# stages_v70.net
KiCad netlist of a schematic drawn in EAGLE
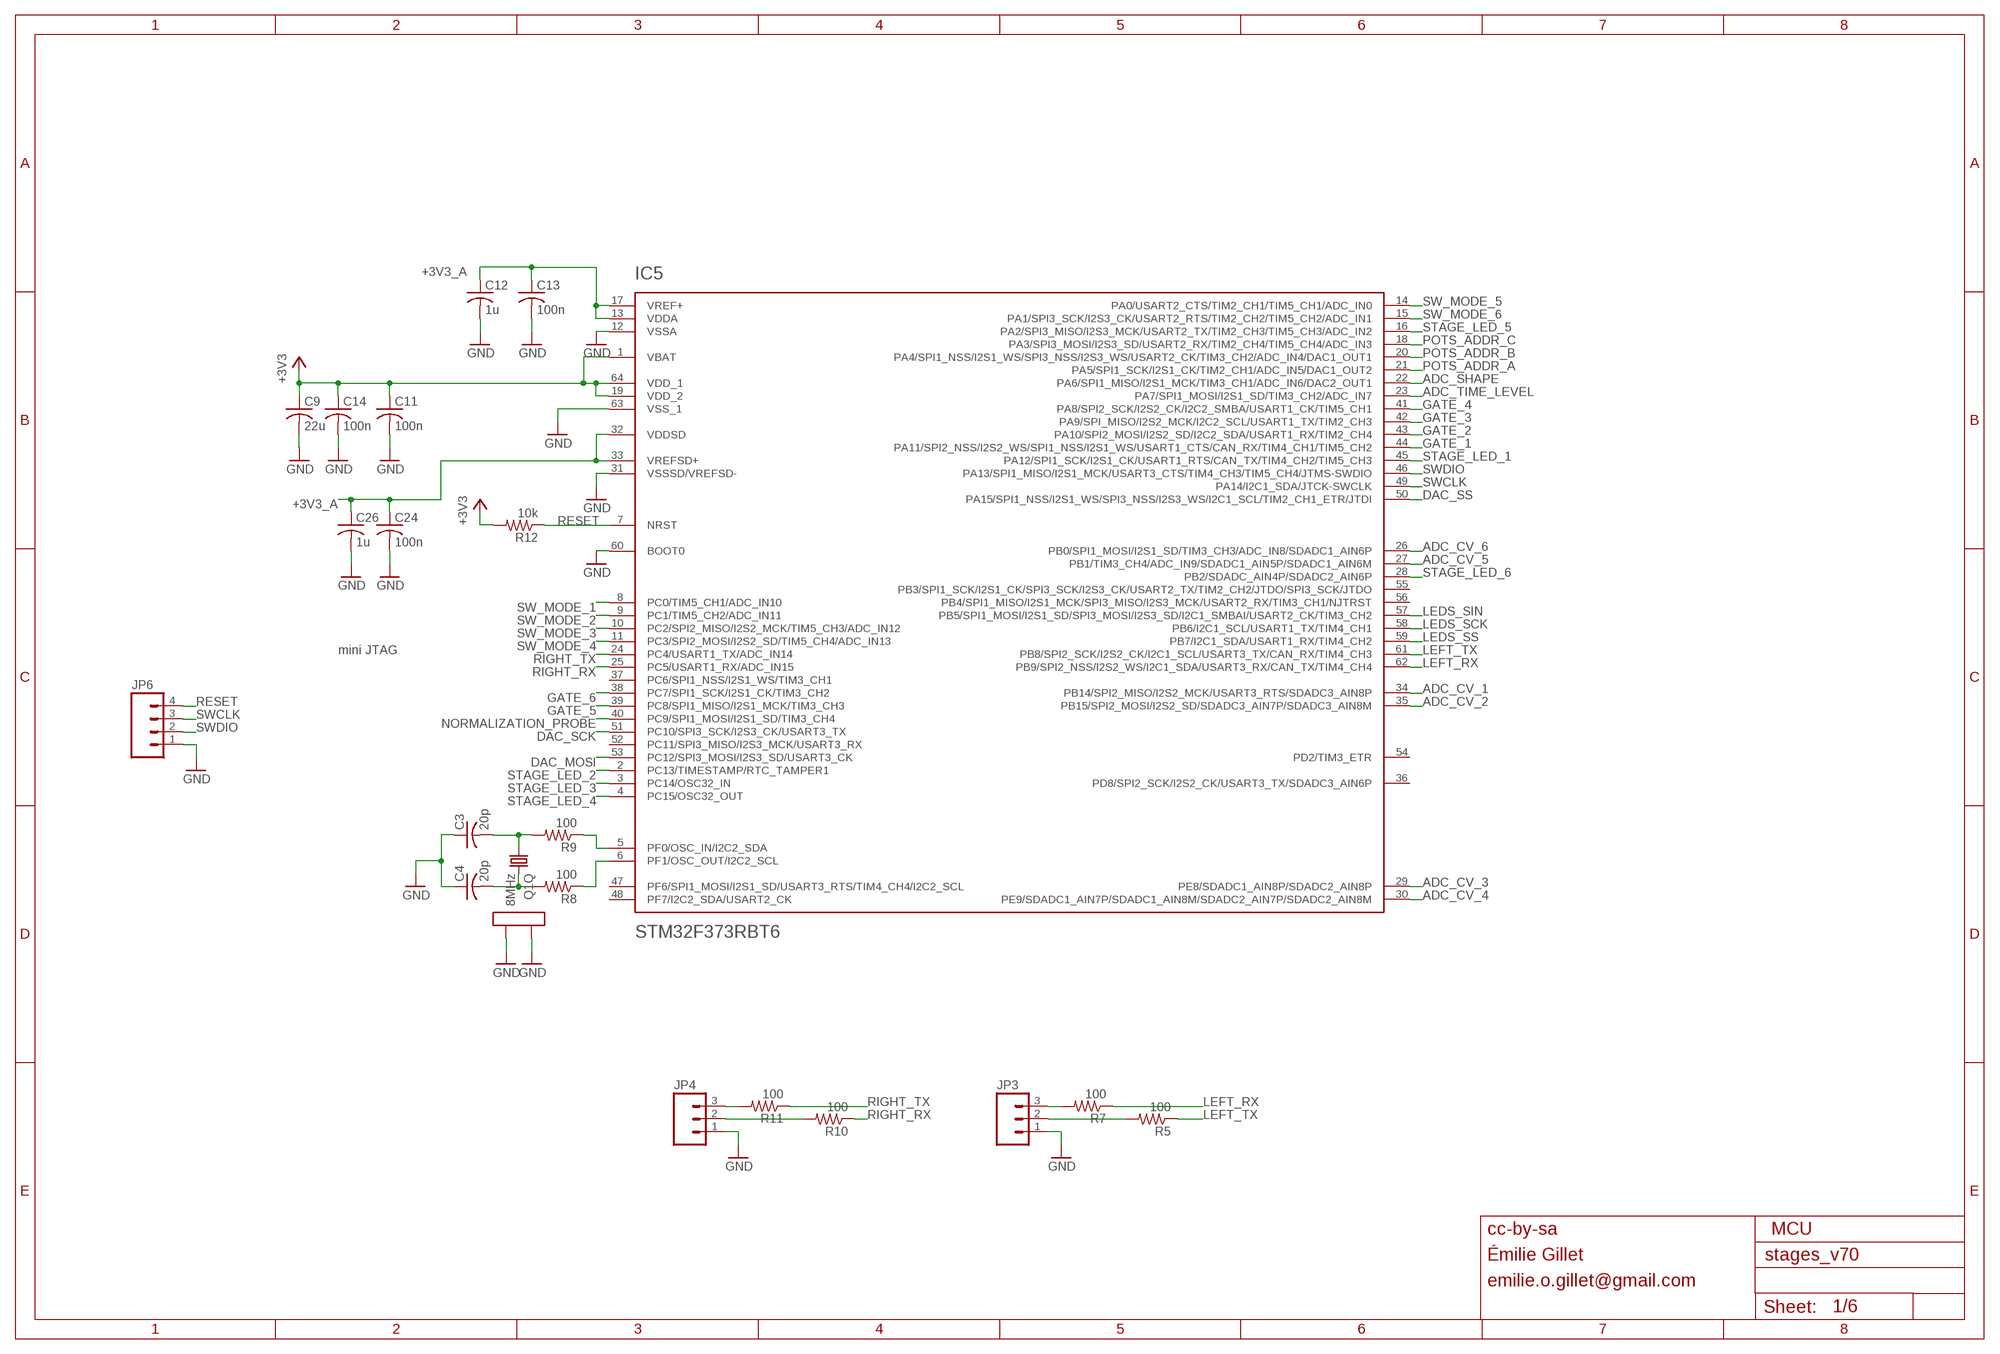
[diagram p0: schematic, sheet 1]
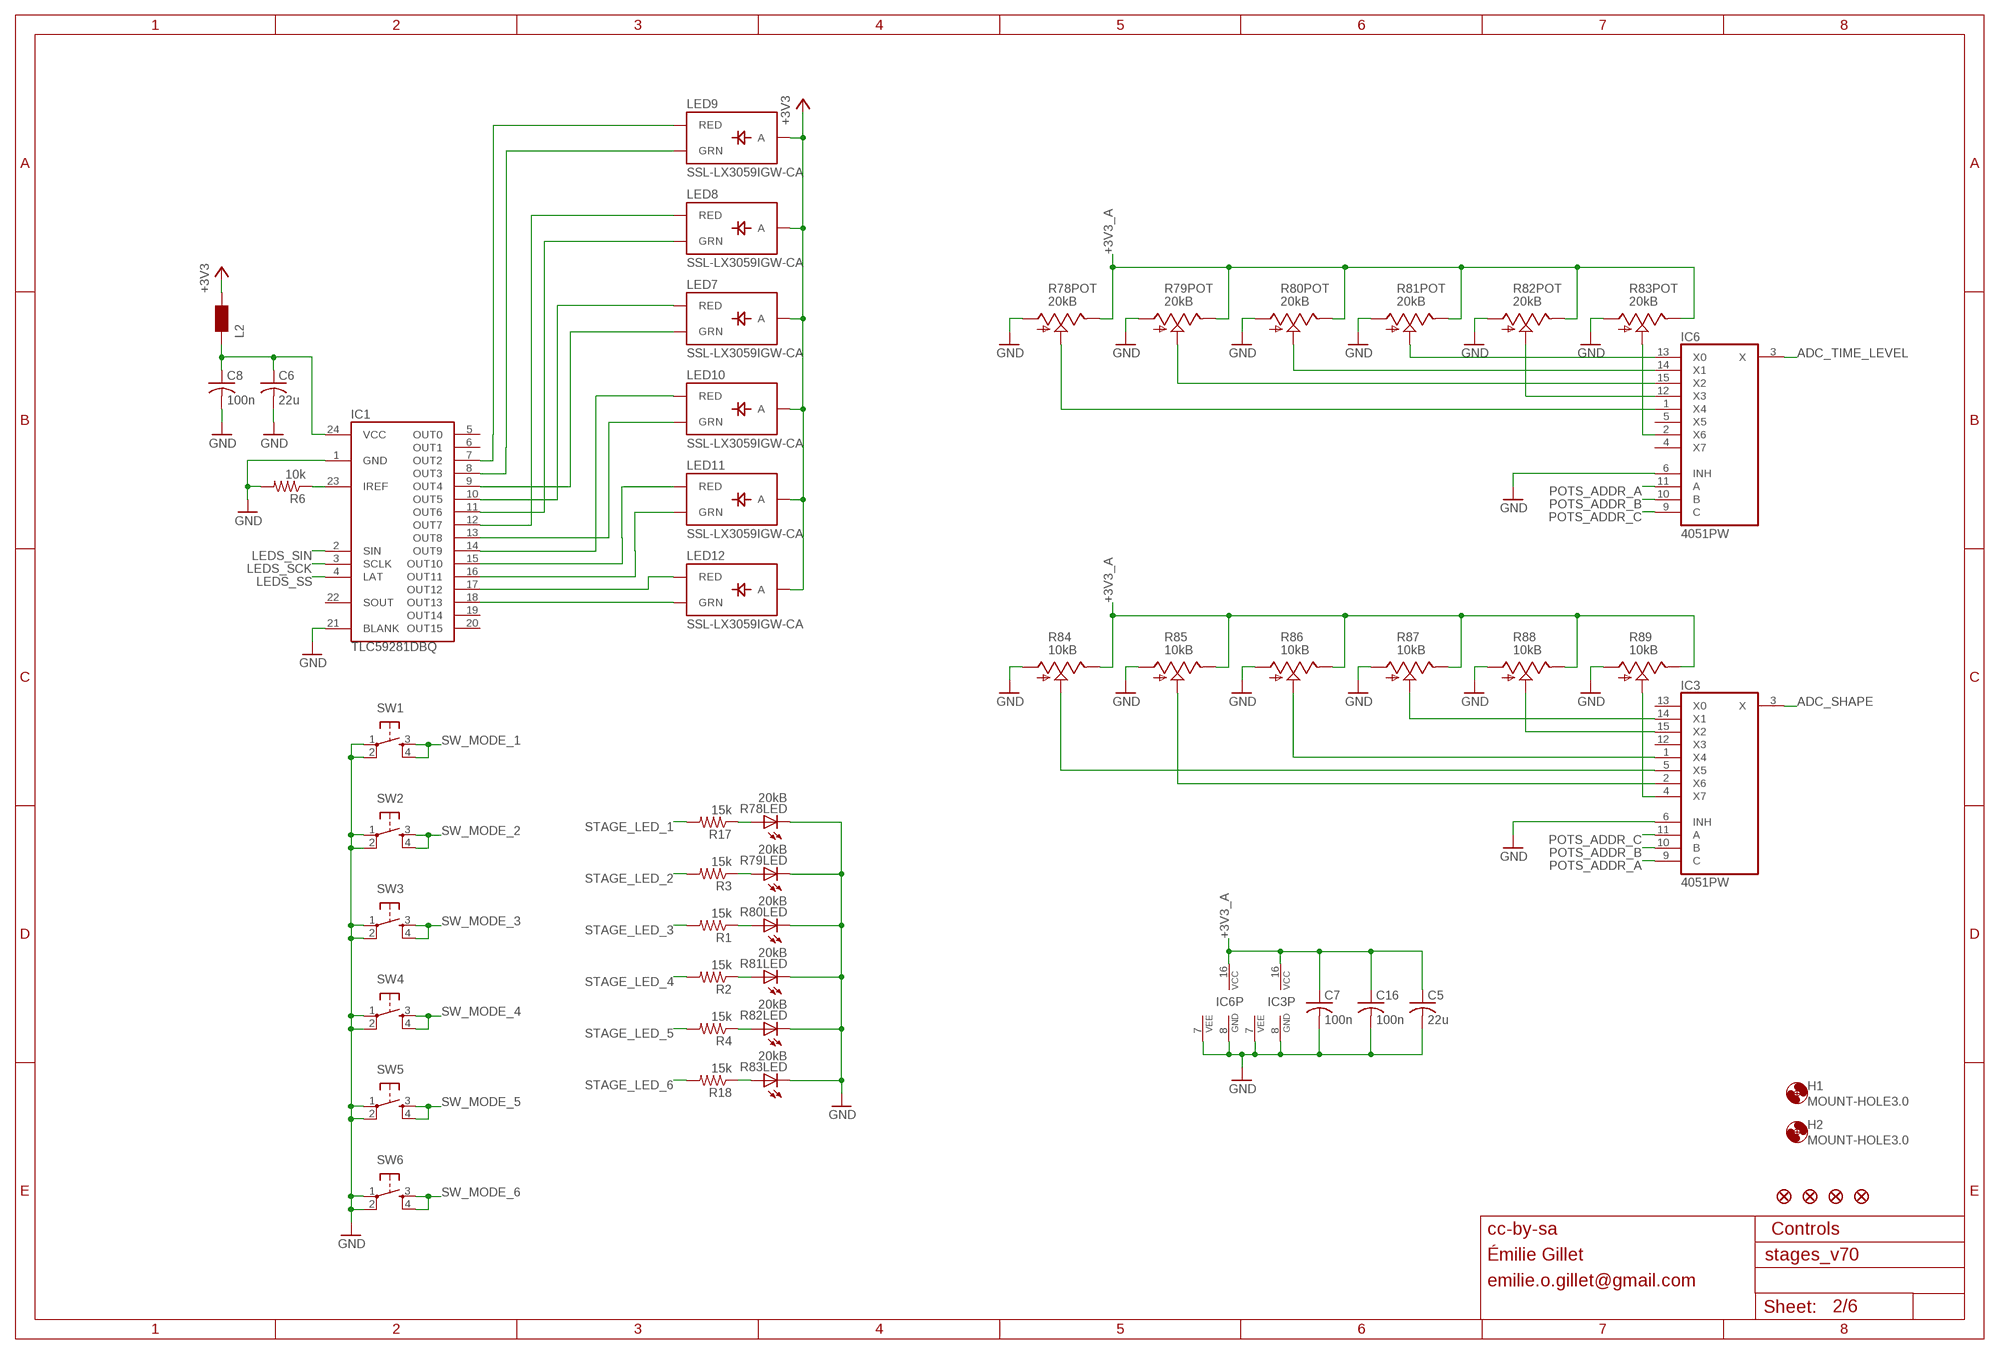
[diagram p1: schematic, sheet 2]
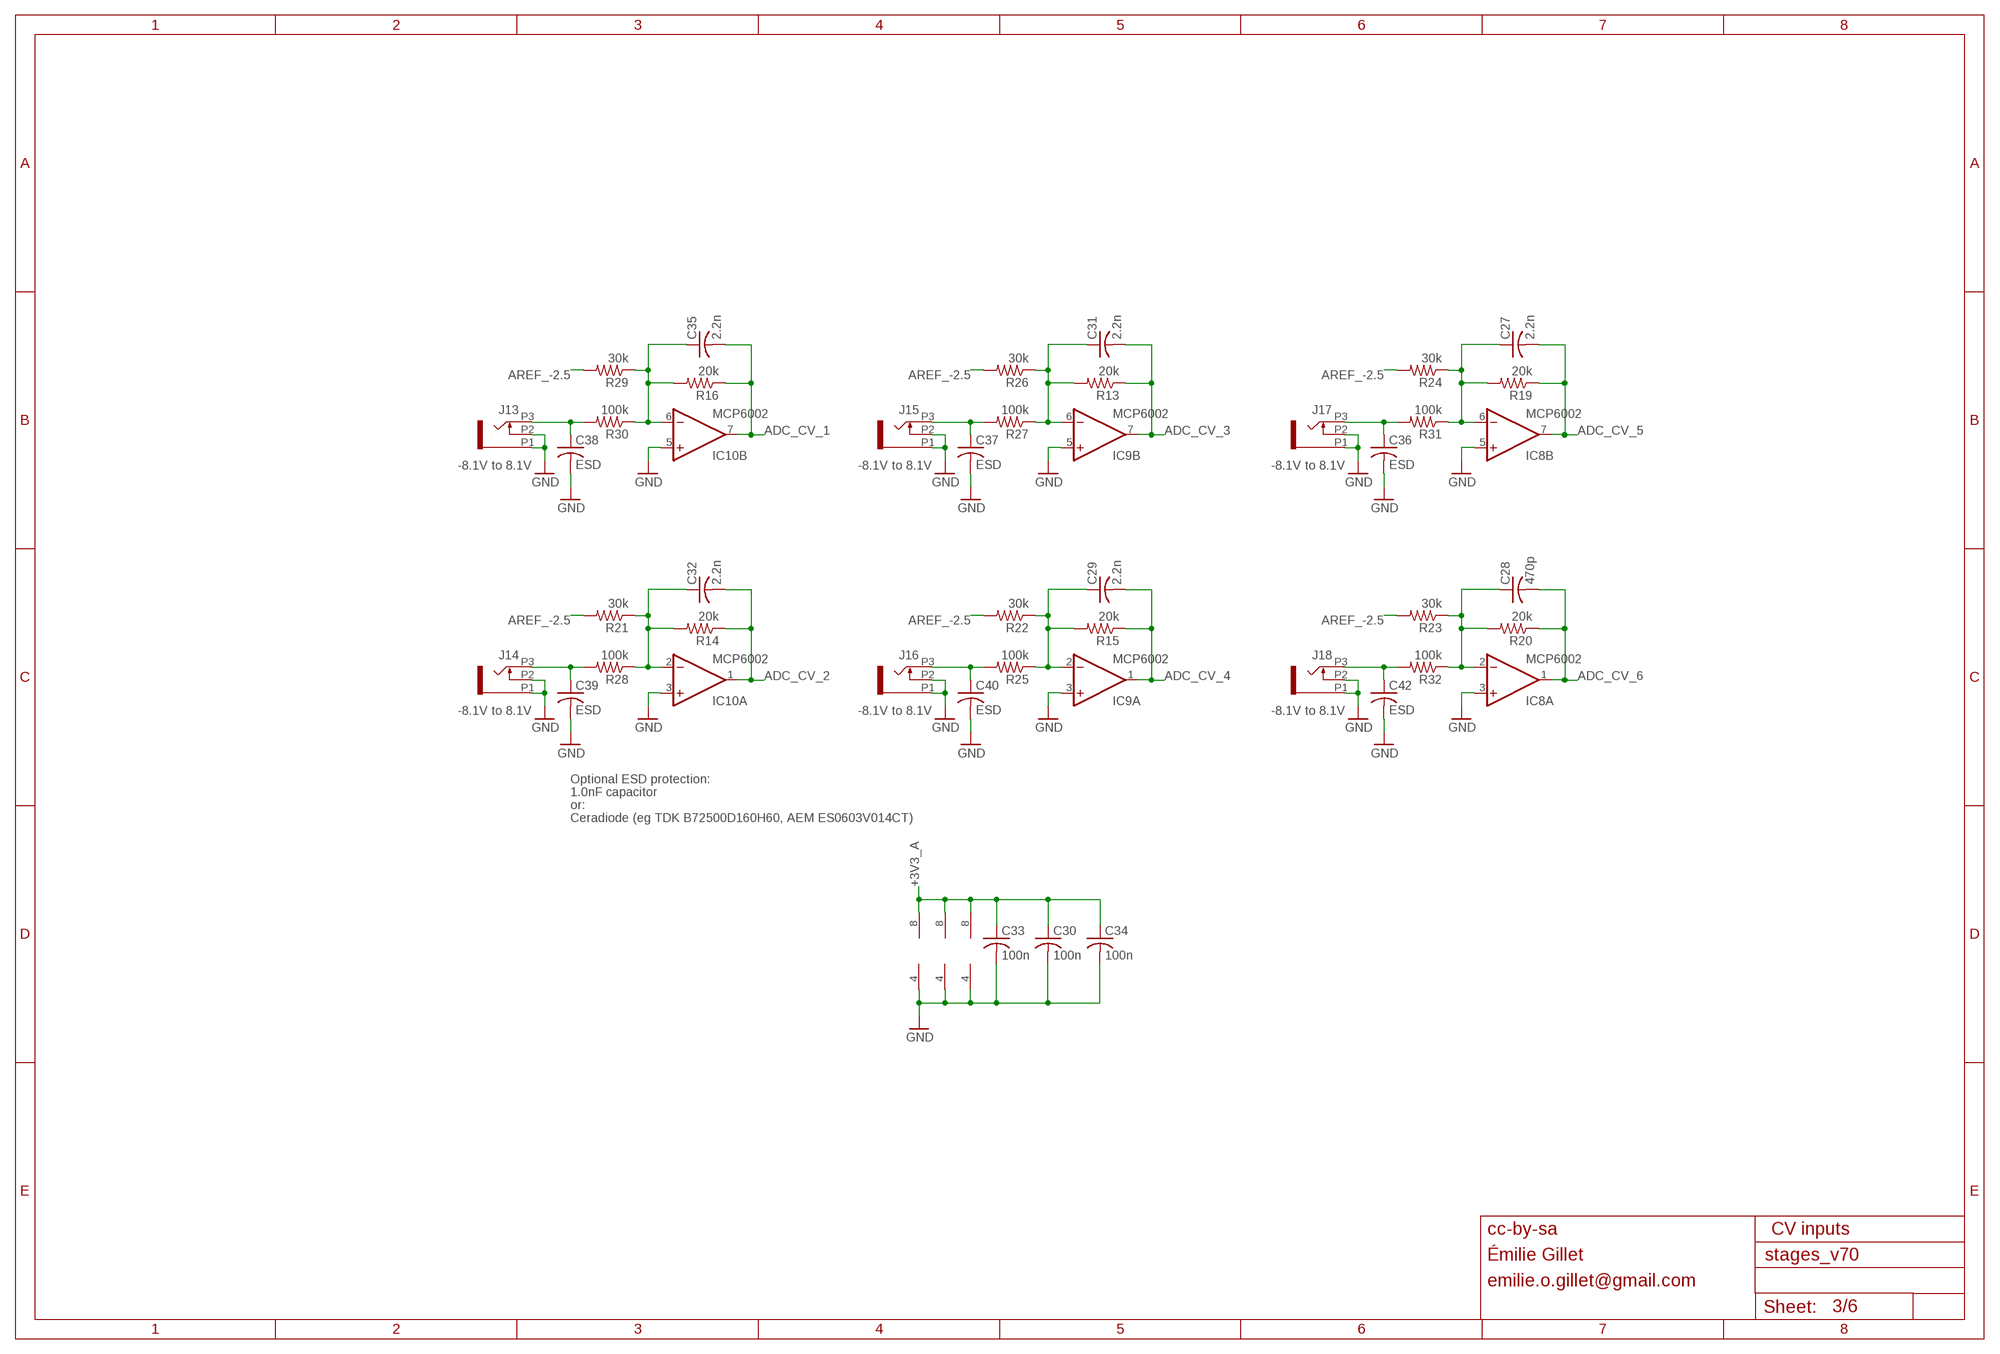
[diagram p2: schematic, sheet 3]
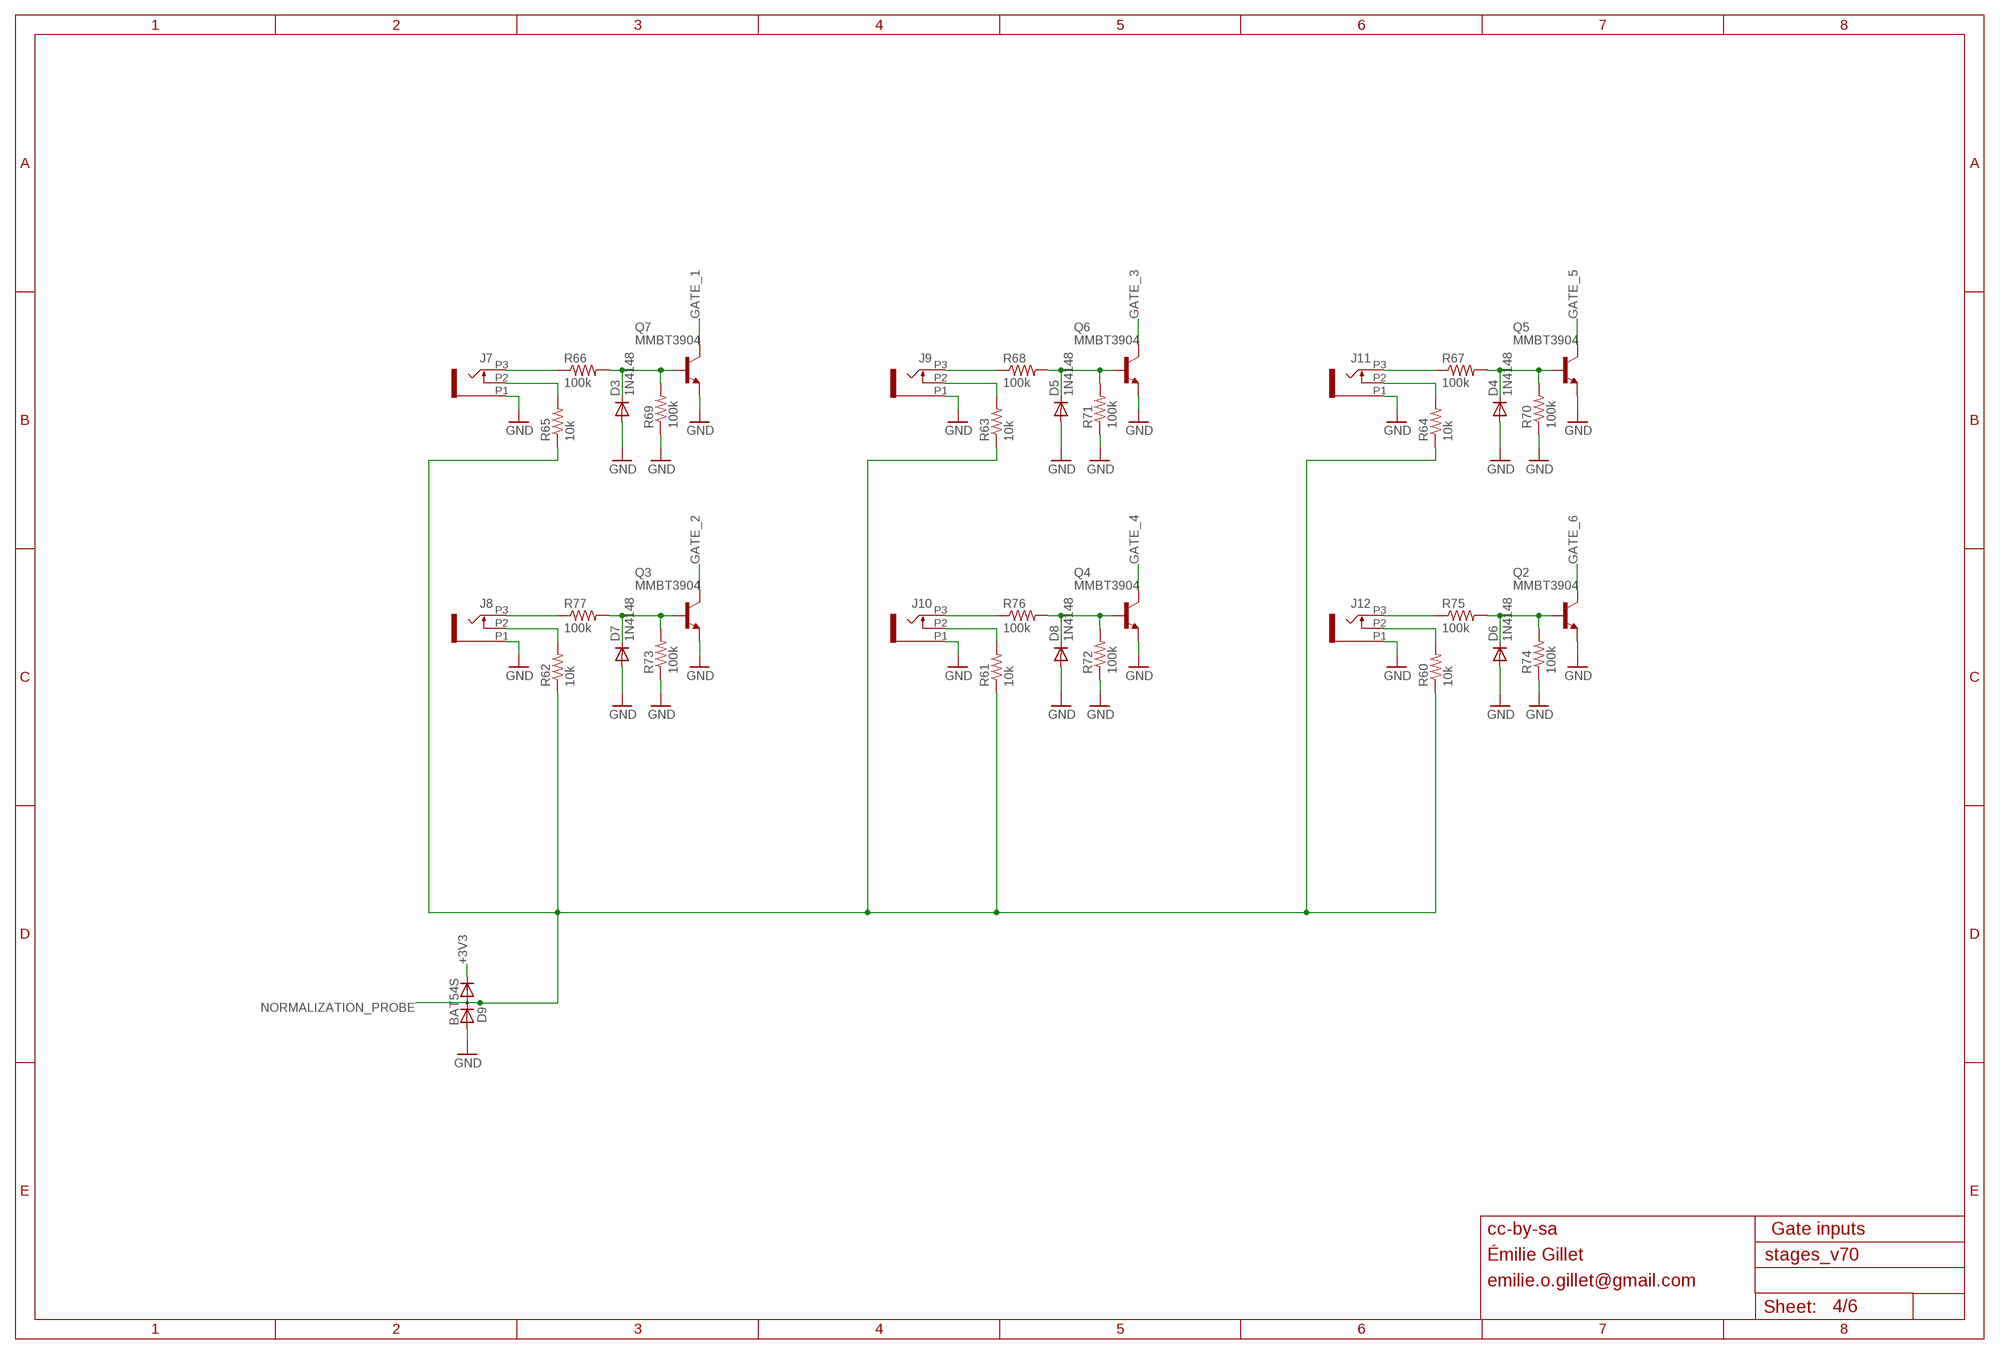
[diagram p3: schematic, sheet 4]
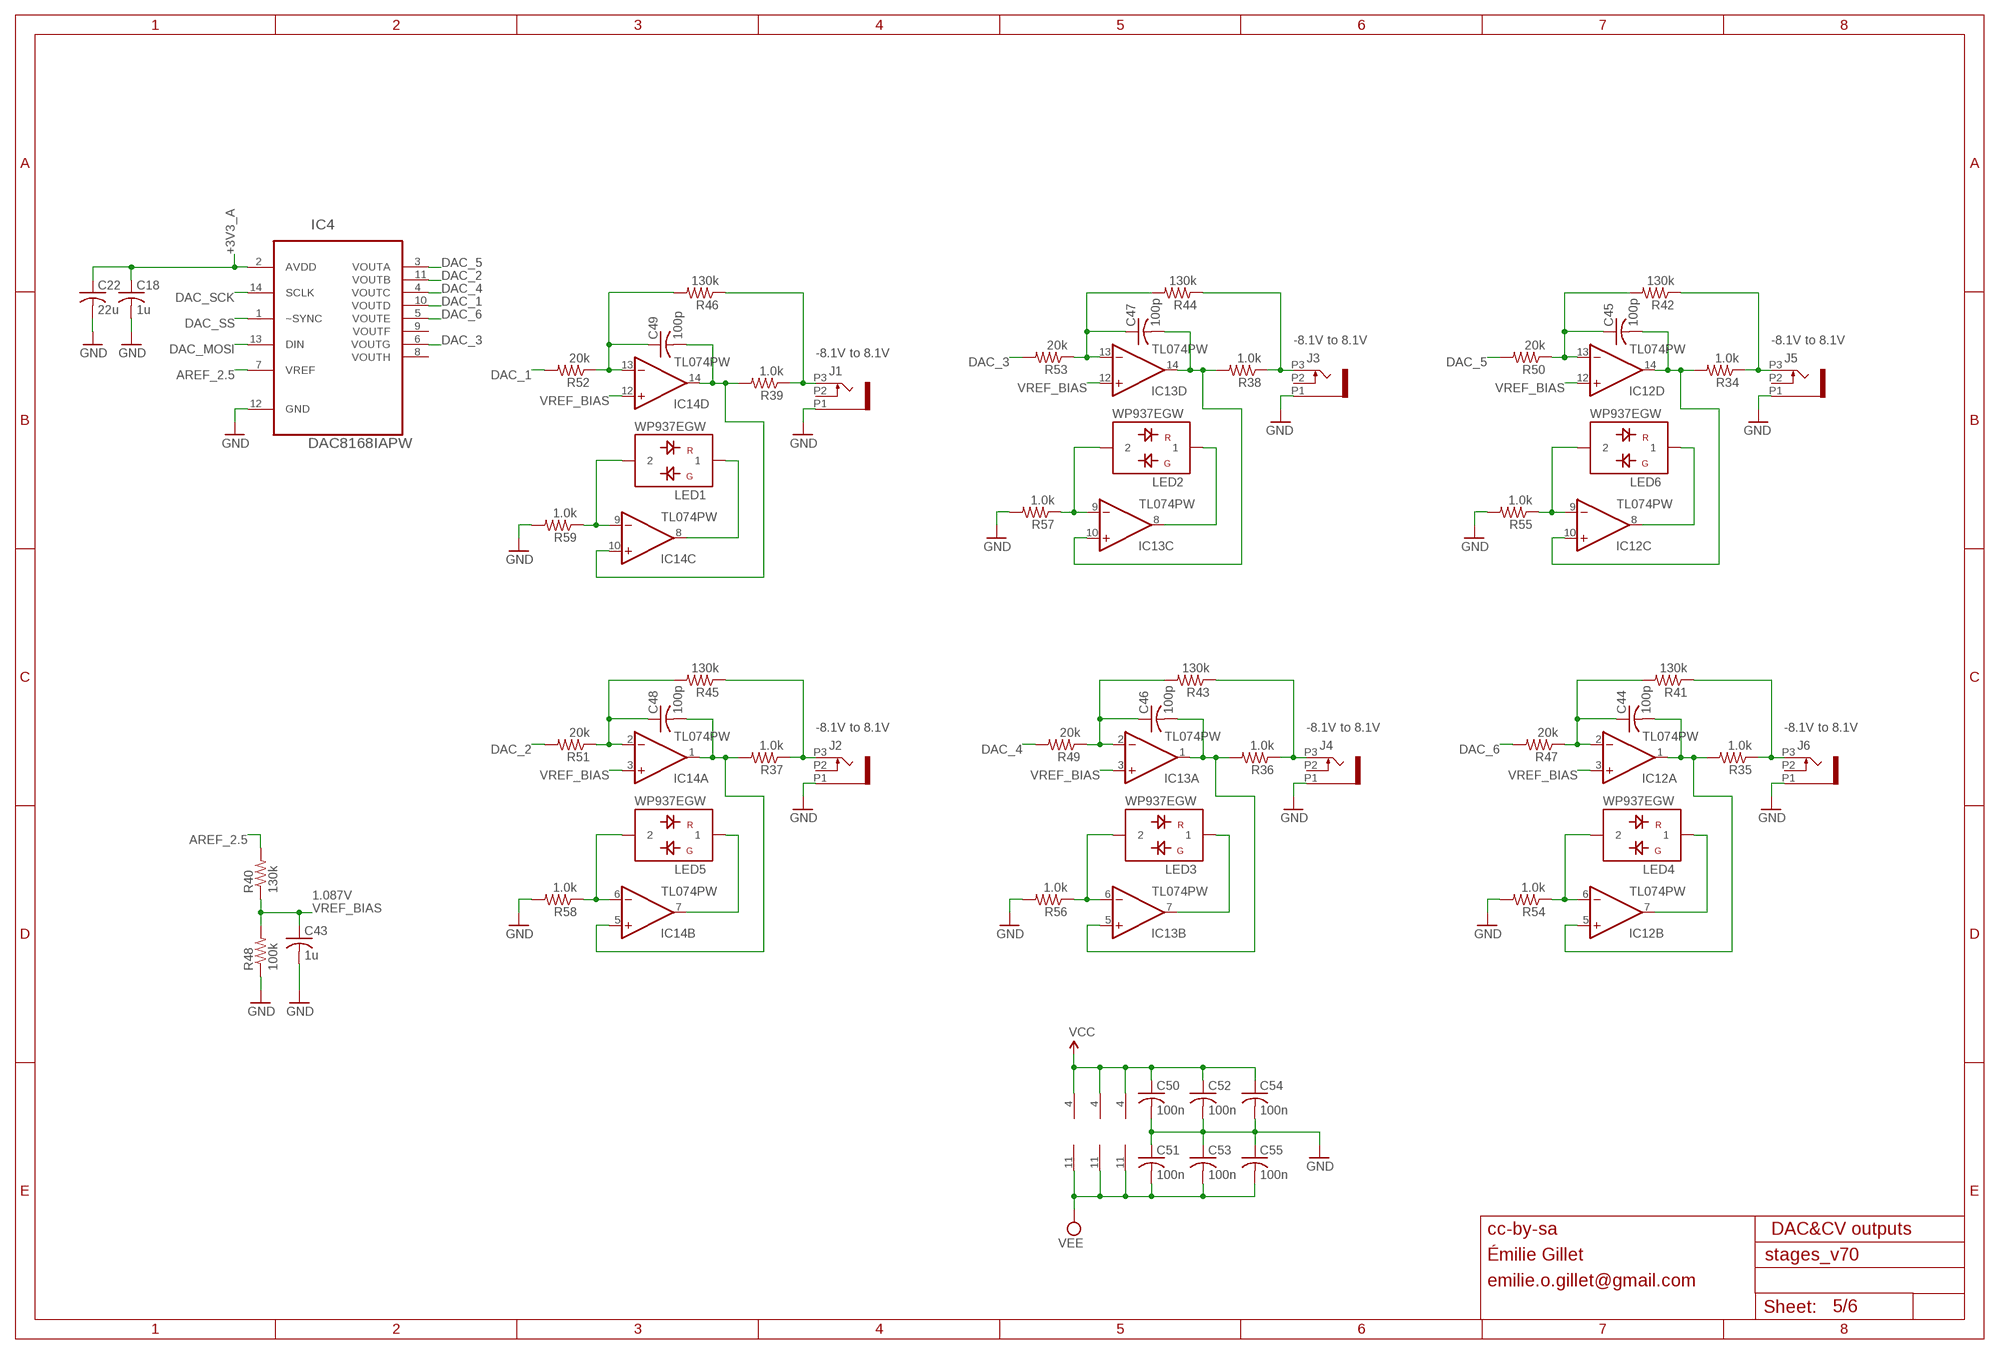
[diagram p4: schematic, sheet 5]
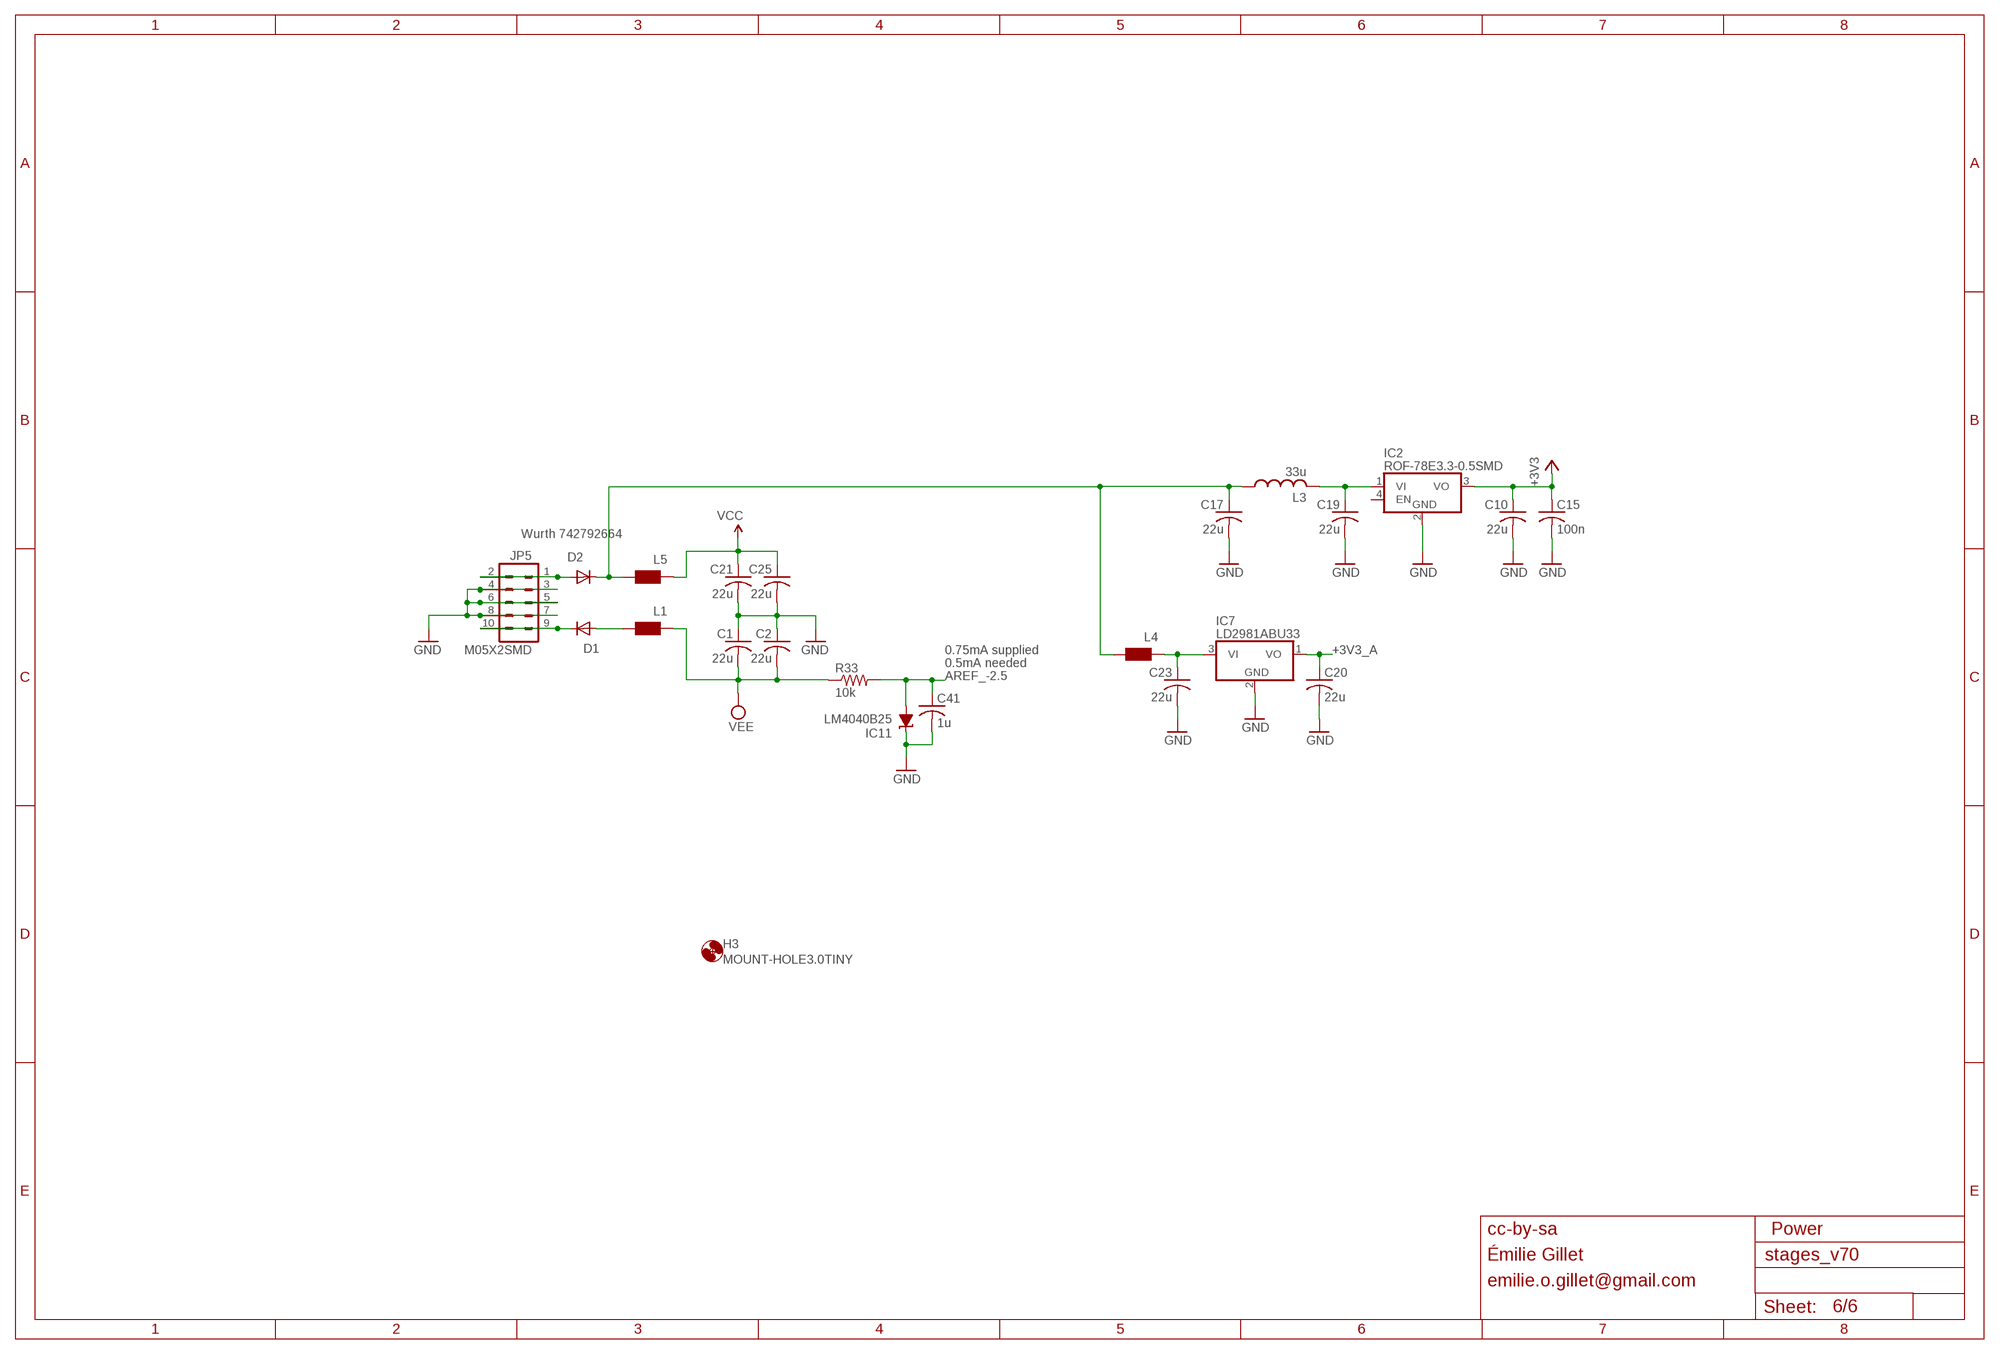
[diagram p5: schematic, sheet 6]

(export (version "E")
  (design (tool "Eeschema 10.0.6"))
  (components
    (comp (ref "C18")
      (value "1u")
      (footprint "eagle-import:C0402")
      (libsource (lib "eagle-import") (part "C-USC0402"))
    )
    (comp (ref "C22")
      (value "22u")
      (footprint "eagle-import:C1206")
      (libsource (lib "eagle-import") (part "C-USC1206"))
    )
    (comp (ref "C43")
      (value "1u")
      (footprint "eagle-import:C0402")
      (libsource (lib "eagle-import") (part "C-USC0402"))
    )
    (comp (ref "C44")
      (value "100p")
      (footprint "eagle-import:C0402")
      (libsource (lib "eagle-import") (part "C-USC0402"))
    )
    (comp (ref "C45")
      (value "100p")
      (footprint "eagle-import:C0402")
      (libsource (lib "eagle-import") (part "C-USC0402"))
    )
    (comp (ref "C46")
      (value "100p")
      (footprint "eagle-import:C0402")
      (libsource (lib "eagle-import") (part "C-USC0402"))
    )
    (comp (ref "C47")
      (value "100p")
      (footprint "eagle-import:C0402")
      (libsource (lib "eagle-import") (part "C-USC0402"))
    )
    (comp (ref "C48")
      (value "100p")
      (footprint "eagle-import:C0402")
      (libsource (lib "eagle-import") (part "C-USC0402"))
    )
    (comp (ref "C49")
      (value "100p")
      (footprint "eagle-import:C0402")
      (libsource (lib "eagle-import") (part "C-USC0402"))
    )
    (comp (ref "C50")
      (value "100n")
      (footprint "eagle-import:C0402")
      (libsource (lib "eagle-import") (part "C-USC0402"))
    )
    (comp (ref "C51")
      (value "100n")
      (footprint "eagle-import:C0402")
      (libsource (lib "eagle-import") (part "C-USC0402"))
    )
    (comp (ref "C52")
      (value "100n")
      (footprint "eagle-import:C0402")
      (libsource (lib "eagle-import") (part "C-USC0402"))
    )
    (comp (ref "C53")
      (value "100n")
      (footprint "eagle-import:C0402")
      (libsource (lib "eagle-import") (part "C-USC0402"))
    )
    (comp (ref "C54")
      (value "100n")
      (footprint "eagle-import:C0402")
      (libsource (lib "eagle-import") (part "C-USC0402"))
    )
    (comp (ref "C55")
      (value "100n")
      (footprint "eagle-import:C0402")
      (libsource (lib "eagle-import") (part "C-USC0402"))
    )
    (comp (ref "IC4")
      (value "DAC8168IAPW")
      (footprint "eagle-import:RPDSOG14")
      (libsource (lib "eagle-import") (part "DAC8168PW"))
    )
    (comp (ref "IC12")
      (value "TL074PW")
      (footprint "eagle-import:TSSOP14_065")
      (libsource (lib "eagle-import") (part "TL074PW"))
    )
    (comp (ref "IC13")
      (value "TL074PW")
      (footprint "eagle-import:TSSOP14_065")
      (libsource (lib "eagle-import") (part "TL074PW"))
    )
    (comp (ref "IC14")
      (value "TL074PW")
      (footprint "eagle-import:TSSOP14_065")
      (libsource (lib "eagle-import") (part "TL074PW"))
    )
    (comp (ref "J1")
      (value "PJ301_THONKICONN6")
      (footprint "eagle-import:WQP_PJ_301M6")
      (libsource (lib "eagle-import") (part "PJ301_THONKICONN6"))
    )
    (comp (ref "J2")
      (value "PJ301_THONKICONN6")
      (footprint "eagle-import:WQP_PJ_301M6")
      (libsource (lib "eagle-import") (part "PJ301_THONKICONN6"))
    )
    (comp (ref "J3")
      (value "PJ301_THONKICONN6")
      (footprint "eagle-import:WQP_PJ_301M6")
      (libsource (lib "eagle-import") (part "PJ301_THONKICONN6"))
    )
    (comp (ref "J4")
      (value "PJ301_THONKICONN6")
      (footprint "eagle-import:WQP_PJ_301M6")
      (libsource (lib "eagle-import") (part "PJ301_THONKICONN6"))
    )
    (comp (ref "J5")
      (value "PJ301_THONKICONN6")
      (footprint "eagle-import:WQP_PJ_301M6")
      (libsource (lib "eagle-import") (part "PJ301_THONKICONN6"))
    )
    (comp (ref "J6")
      (value "PJ301_THONKICONN6")
      (footprint "eagle-import:WQP_PJ_301M6")
      (libsource (lib "eagle-import") (part "PJ301_THONKICONN6"))
    )
    (comp (ref "LED1")
      (value "WP937EGW")
      (footprint "eagle-import:LED3MM")
      (libsource (lib "eagle-import") (part "LED-BICOLOR-SHARED-THROUGHHOLE"))
    )
    (comp (ref "LED2")
      (value "WP937EGW")
      (footprint "eagle-import:LED3MM")
      (libsource (lib "eagle-import") (part "LED-BICOLOR-SHARED-THROUGHHOLE"))
    )
    (comp (ref "LED3")
      (value "WP937EGW")
      (footprint "eagle-import:LED3MM")
      (libsource (lib "eagle-import") (part "LED-BICOLOR-SHARED-THROUGHHOLE"))
    )
    (comp (ref "LED4")
      (value "WP937EGW")
      (footprint "eagle-import:LED3MM")
      (libsource (lib "eagle-import") (part "LED-BICOLOR-SHARED-THROUGHHOLE"))
    )
    (comp (ref "LED5")
      (value "WP937EGW")
      (footprint "eagle-import:LED3MM")
      (libsource (lib "eagle-import") (part "LED-BICOLOR-SHARED-THROUGHHOLE"))
    )
    (comp (ref "LED6")
      (value "WP937EGW")
      (footprint "eagle-import:LED3MM")
      (libsource (lib "eagle-import") (part "LED-BICOLOR-SHARED-THROUGHHOLE"))
    )
    (comp (ref "R34")
      (value "1.0k")
      (footprint "eagle-import:R0603")
      (libsource (lib "eagle-import") (part "R-US_R0603"))
    )
    (comp (ref "R35")
      (value "1.0k")
      (footprint "eagle-import:R0603")
      (libsource (lib "eagle-import") (part "R-US_R0603"))
    )
    (comp (ref "R36")
      (value "1.0k")
      (footprint "eagle-import:R0603")
      (libsource (lib "eagle-import") (part "R-US_R0603"))
    )
    (comp (ref "R37")
      (value "1.0k")
      (footprint "eagle-import:R0603")
      (libsource (lib "eagle-import") (part "R-US_R0603"))
    )
    (comp (ref "R38")
      (value "1.0k")
      (footprint "eagle-import:R0603")
      (libsource (lib "eagle-import") (part "R-US_R0603"))
    )
    (comp (ref "R39")
      (value "1.0k")
      (footprint "eagle-import:R0603")
      (libsource (lib "eagle-import") (part "R-US_R0603"))
    )
    (comp (ref "R40")
      (value "130k")
      (footprint "eagle-import:R0402")
      (libsource (lib "eagle-import") (part "R-US_R0402"))
    )
    (comp (ref "R41")
      (value "130k")
      (footprint "eagle-import:R0402")
      (libsource (lib "eagle-import") (part "R-US_R0402"))
    )
    (comp (ref "R42")
      (value "130k")
      (footprint "eagle-import:R0402")
      (libsource (lib "eagle-import") (part "R-US_R0402"))
    )
    (comp (ref "R43")
      (value "130k")
      (footprint "eagle-import:R0402")
      (libsource (lib "eagle-import") (part "R-US_R0402"))
    )
    (comp (ref "R44")
      (value "130k")
      (footprint "eagle-import:R0402")
      (libsource (lib "eagle-import") (part "R-US_R0402"))
    )
    (comp (ref "R45")
      (value "130k")
      (footprint "eagle-import:R0402")
      (libsource (lib "eagle-import") (part "R-US_R0402"))
    )
    (comp (ref "R46")
      (value "130k")
      (footprint "eagle-import:R0402")
      (libsource (lib "eagle-import") (part "R-US_R0402"))
    )
    (comp (ref "R47")
      (value "20k")
      (footprint "eagle-import:R0402")
      (libsource (lib "eagle-import") (part "R-US_R0402"))
    )
    (comp (ref "R48")
      (value "100k")
      (footprint "eagle-import:R0402")
      (libsource (lib "eagle-import") (part "R-US_R0402"))
    )
    (comp (ref "R49")
      (value "20k")
      (footprint "eagle-import:R0402")
      (libsource (lib "eagle-import") (part "R-US_R0402"))
    )
    (comp (ref "R50")
      (value "20k")
      (footprint "eagle-import:R0402")
      (libsource (lib "eagle-import") (part "R-US_R0402"))
    )
    (comp (ref "R51")
      (value "20k")
      (footprint "eagle-import:R0402")
      (libsource (lib "eagle-import") (part "R-US_R0402"))
    )
    (comp (ref "R52")
      (value "20k")
      (footprint "eagle-import:R0402")
      (libsource (lib "eagle-import") (part "R-US_R0402"))
    )
    (comp (ref "R53")
      (value "20k")
      (footprint "eagle-import:R0402")
      (libsource (lib "eagle-import") (part "R-US_R0402"))
    )
    (comp (ref "R54")
      (value "1.0k")
      (footprint "eagle-import:R0402")
      (libsource (lib "eagle-import") (part "R-US_R0402"))
    )
    (comp (ref "R55")
      (value "1.0k")
      (footprint "eagle-import:R0402")
      (libsource (lib "eagle-import") (part "R-US_R0402"))
    )
    (comp (ref "R56")
      (value "1.0k")
      (footprint "eagle-import:R0402")
      (libsource (lib "eagle-import") (part "R-US_R0402"))
    )
    (comp (ref "R57")
      (value "1.0k")
      (footprint "eagle-import:R0402")
      (libsource (lib "eagle-import") (part "R-US_R0402"))
    )
    (comp (ref "R58")
      (value "1.0k")
      (footprint "eagle-import:R0402")
      (libsource (lib "eagle-import") (part "R-US_R0402"))
    )
    (comp (ref "R59")
      (value "1.0k")
      (footprint "eagle-import:R0402")
      (libsource (lib "eagle-import") (part "R-US_R0402"))
    )
    (comp (ref "C27")
      (value "2.2n")
      (footprint "eagle-import:C0402")
      (libsource (lib "eagle-import") (part "C-USC0402"))
    )
    (comp (ref "C28")
      (value "470p")
      (footprint "eagle-import:C0402")
      (libsource (lib "eagle-import") (part "C-USC0402"))
    )
    (comp (ref "C29")
      (value "2.2n")
      (footprint "eagle-import:C0402")
      (libsource (lib "eagle-import") (part "C-USC0402"))
    )
    (comp (ref "C30")
      (value "100n")
      (footprint "eagle-import:C0402")
      (libsource (lib "eagle-import") (part "C-USC0402"))
    )
    (comp (ref "C31")
      (value "2.2n")
      (footprint "eagle-import:C0402")
      (libsource (lib "eagle-import") (part "C-USC0402"))
    )
    (comp (ref "C32")
      (value "2.2n")
      (footprint "eagle-import:C0402")
      (libsource (lib "eagle-import") (part "C-USC0402"))
    )
    (comp (ref "C33")
      (value "100n")
      (footprint "eagle-import:C0402")
      (libsource (lib "eagle-import") (part "C-USC0402"))
    )
    (comp (ref "C34")
      (value "100n")
      (footprint "eagle-import:C0402")
      (libsource (lib "eagle-import") (part "C-USC0402"))
    )
    (comp (ref "C35")
      (value "2.2n")
      (footprint "eagle-import:C0402")
      (libsource (lib "eagle-import") (part "C-USC0402"))
    )
    (comp (ref "C36")
      (value "ESD")
      (footprint "eagle-import:C0603")
      (libsource (lib "eagle-import") (part "C-USC0603"))
    )
    (comp (ref "C37")
      (value "ESD")
      (footprint "eagle-import:C0603")
      (libsource (lib "eagle-import") (part "C-USC0603"))
    )
    (comp (ref "C38")
      (value "ESD")
      (footprint "eagle-import:C0603")
      (libsource (lib "eagle-import") (part "C-USC0603"))
    )
    (comp (ref "C39")
      (value "ESD")
      (footprint "eagle-import:C0603")
      (libsource (lib "eagle-import") (part "C-USC0603"))
    )
    (comp (ref "C40")
      (value "ESD")
      (footprint "eagle-import:C0603")
      (libsource (lib "eagle-import") (part "C-USC0603"))
    )
    (comp (ref "C42")
      (value "ESD")
      (footprint "eagle-import:C0603")
      (libsource (lib "eagle-import") (part "C-USC0603"))
    )
    (comp (ref "IC8")
      (value "MCP6002")
      (footprint "eagle-import:MSOP-8")
      (libsource (lib "eagle-import") (part "OPA1652DGK"))
    )
    (comp (ref "IC9")
      (value "MCP6002")
      (footprint "eagle-import:MSOP-8")
      (libsource (lib "eagle-import") (part "OPA1652DGK"))
    )
    (comp (ref "IC10")
      (value "MCP6002")
      (footprint "eagle-import:MSOP-8")
      (libsource (lib "eagle-import") (part "OPA1652DGK"))
    )
    (comp (ref "J13")
      (value "PJ301_THONKICONN6")
      (footprint "eagle-import:WQP_PJ_301M6")
      (libsource (lib "eagle-import") (part "PJ301_THONKICONN6"))
    )
    (comp (ref "J14")
      (value "PJ301_THONKICONN6")
      (footprint "eagle-import:WQP_PJ_301M6")
      (libsource (lib "eagle-import") (part "PJ301_THONKICONN6"))
    )
    (comp (ref "J15")
      (value "PJ301_THONKICONN6")
      (footprint "eagle-import:WQP_PJ_301M6")
      (libsource (lib "eagle-import") (part "PJ301_THONKICONN6"))
    )
    (comp (ref "J16")
      (value "PJ301_THONKICONN6")
      (footprint "eagle-import:WQP_PJ_301M6")
      (libsource (lib "eagle-import") (part "PJ301_THONKICONN6"))
    )
    (comp (ref "J17")
      (value "PJ301_THONKICONN6")
      (footprint "eagle-import:WQP_PJ_301M6")
      (libsource (lib "eagle-import") (part "PJ301_THONKICONN6"))
    )
    (comp (ref "J18")
      (value "PJ301_THONKICONN6")
      (footprint "eagle-import:WQP_PJ_301M6")
      (libsource (lib "eagle-import") (part "PJ301_THONKICONN6"))
    )
    (comp (ref "R13")
      (value "20k")
      (footprint "eagle-import:R0402")
      (libsource (lib "eagle-import") (part "R-US_R0402"))
    )
    (comp (ref "R14")
      (value "20k")
      (footprint "eagle-import:R0402")
      (libsource (lib "eagle-import") (part "R-US_R0402"))
    )
    (comp (ref "R15")
      (value "20k")
      (footprint "eagle-import:R0402")
      (libsource (lib "eagle-import") (part "R-US_R0402"))
    )
    (comp (ref "R16")
      (value "20k")
      (footprint "eagle-import:R0402")
      (libsource (lib "eagle-import") (part "R-US_R0402"))
    )
    (comp (ref "R19")
      (value "20k")
      (footprint "eagle-import:R0402")
      (libsource (lib "eagle-import") (part "R-US_R0402"))
    )
    (comp (ref "R20")
      (value "20k")
      (footprint "eagle-import:R0402")
      (libsource (lib "eagle-import") (part "R-US_R0402"))
    )
    (comp (ref "R21")
      (value "30k")
      (footprint "eagle-import:R0402")
      (libsource (lib "eagle-import") (part "R-US_R0402"))
    )
    (comp (ref "R22")
      (value "30k")
      (footprint "eagle-import:R0402")
      (libsource (lib "eagle-import") (part "R-US_R0402"))
    )
    (comp (ref "R23")
      (value "30k")
      (footprint "eagle-import:R0402")
      (libsource (lib "eagle-import") (part "R-US_R0402"))
    )
    (comp (ref "R24")
      (value "30k")
      (footprint "eagle-import:R0402")
      (libsource (lib "eagle-import") (part "R-US_R0402"))
    )
    (comp (ref "R25")
      (value "100k")
      (footprint "eagle-import:R0402")
      (libsource (lib "eagle-import") (part "R-US_R0402"))
    )
    (comp (ref "R26")
      (value "30k")
      (footprint "eagle-import:R0402")
      (libsource (lib "eagle-import") (part "R-US_R0402"))
    )
    (comp (ref "R27")
      (value "100k")
      (footprint "eagle-import:R0402")
      (libsource (lib "eagle-import") (part "R-US_R0402"))
    )
    (comp (ref "R28")
      (value "100k")
      (footprint "eagle-import:R0402")
      (libsource (lib "eagle-import") (part "R-US_R0402"))
    )
    (comp (ref "R29")
      (value "30k")
      (footprint "eagle-import:R0402")
      (libsource (lib "eagle-import") (part "R-US_R0402"))
    )
    (comp (ref "R30")
      (value "100k")
      (footprint "eagle-import:R0402")
      (libsource (lib "eagle-import") (part "R-US_R0402"))
    )
    (comp (ref "R31")
      (value "100k")
      (footprint "eagle-import:R0402")
      (libsource (lib "eagle-import") (part "R-US_R0402"))
    )
    (comp (ref "R32")
      (value "100k")
      (footprint "eagle-import:R0402")
      (libsource (lib "eagle-import") (part "R-US_R0402"))
    )
    (comp (ref "C3")
      (value "20p")
      (footprint "eagle-import:C0402")
      (libsource (lib "eagle-import") (part "C-USC0402"))
    )
    (comp (ref "C4")
      (value "20p")
      (footprint "eagle-import:C0402")
      (libsource (lib "eagle-import") (part "C-USC0402"))
    )
    (comp (ref "C9")
      (value "22u")
      (footprint "eagle-import:C1206")
      (libsource (lib "eagle-import") (part "C-USC1206"))
    )
    (comp (ref "C11")
      (value "100n")
      (footprint "eagle-import:C0402")
      (libsource (lib "eagle-import") (part "C-USC0402"))
    )
    (comp (ref "C12")
      (value "1u")
      (footprint "eagle-import:C0402")
      (libsource (lib "eagle-import") (part "C-USC0402"))
    )
    (comp (ref "C13")
      (value "100n")
      (footprint "eagle-import:C0402")
      (libsource (lib "eagle-import") (part "C-USC0402"))
    )
    (comp (ref "C14")
      (value "100n")
      (footprint "eagle-import:C0402")
      (libsource (lib "eagle-import") (part "C-USC0402"))
    )
    (comp (ref "C24")
      (value "100n")
      (footprint "eagle-import:C0402")
      (libsource (lib "eagle-import") (part "C-USC0402"))
    )
    (comp (ref "C26")
      (value "1u")
      (footprint "eagle-import:C0402")
      (libsource (lib "eagle-import") (part "C-USC0402"))
    )
    (comp (ref "IC5")
      (value "STM32F373RBT6")
      (footprint "eagle-import:TQFP-10X10-64")
      (libsource (lib "eagle-import") (part "STM32F373R"))
    )
    (comp (ref "JP3")
      (value "M03PTH")
      (footprint "eagle-import:1X03")
      (libsource (lib "eagle-import") (part "M03PTH"))
    )
    (comp (ref "JP4")
      (value "M03PTH")
      (footprint "eagle-import:1X03")
      (libsource (lib "eagle-import") (part "M03PTH"))
    )
    (comp (ref "JP6")
      (value "M04PTH")
      (footprint "eagle-import:1X04")
      (libsource (lib "eagle-import") (part "M04PTH"))
    )
    (comp (ref "Q1")
      (value "8MHz")
      (footprint "eagle-import:CTS406")
      (libsource (lib "eagle-import") (part "CRYSTAL"))
    )
    (comp (ref "R5")
      (value "100")
      (footprint "eagle-import:R0402")
      (libsource (lib "eagle-import") (part "R-US_R0402"))
    )
    (comp (ref "R7")
      (value "100")
      (footprint "eagle-import:R0402")
      (libsource (lib "eagle-import") (part "R-US_R0402"))
    )
    (comp (ref "R8")
      (value "100")
      (footprint "eagle-import:R0402")
      (libsource (lib "eagle-import") (part "R-US_R0402"))
    )
    (comp (ref "R9")
      (value "100")
      (footprint "eagle-import:R0402")
      (libsource (lib "eagle-import") (part "R-US_R0402"))
    )
    (comp (ref "R10")
      (value "100")
      (footprint "eagle-import:R0402")
      (libsource (lib "eagle-import") (part "R-US_R0402"))
    )
    (comp (ref "R11")
      (value "100")
      (footprint "eagle-import:R0402")
      (libsource (lib "eagle-import") (part "R-US_R0402"))
    )
    (comp (ref "R12")
      (value "10k")
      (footprint "eagle-import:R0402")
      (libsource (lib "eagle-import") (part "R-US_R0402"))
    )
    (comp (ref "D3")
      (value "1N4148")
      (footprint "eagle-import:SOD523")
      (libsource (lib "eagle-import") (part "DIODE-SOD523"))
    )
    (comp (ref "D4")
      (value "1N4148")
      (footprint "eagle-import:SOD523")
      (libsource (lib "eagle-import") (part "DIODE-SOD523"))
    )
    (comp (ref "D5")
      (value "1N4148")
      (footprint "eagle-import:SOD523")
      (libsource (lib "eagle-import") (part "DIODE-SOD523"))
    )
    (comp (ref "D6")
      (value "1N4148")
      (footprint "eagle-import:SOD523")
      (libsource (lib "eagle-import") (part "DIODE-SOD523"))
    )
    (comp (ref "D7")
      (value "1N4148")
      (footprint "eagle-import:SOD523")
      (libsource (lib "eagle-import") (part "DIODE-SOD523"))
    )
    (comp (ref "D8")
      (value "1N4148")
      (footprint "eagle-import:SOD523")
      (libsource (lib "eagle-import") (part "DIODE-SOD523"))
    )
    (comp (ref "D9")
      (value "BAT54S")
      (footprint "eagle-import:SOT23")
      (libsource (lib "eagle-import") (part "DIODE_2CACA-SOT23"))
    )
    (comp (ref "J7")
      (value "PJ301_THONKICONN6")
      (footprint "eagle-import:WQP_PJ_301M6")
      (libsource (lib "eagle-import") (part "PJ301_THONKICONN6"))
    )
    (comp (ref "J8")
      (value "PJ301_THONKICONN6")
      (footprint "eagle-import:WQP_PJ_301M6")
      (libsource (lib "eagle-import") (part "PJ301_THONKICONN6"))
    )
    (comp (ref "J9")
      (value "PJ301_THONKICONN6")
      (footprint "eagle-import:WQP_PJ_301M6")
      (libsource (lib "eagle-import") (part "PJ301_THONKICONN6"))
    )
    (comp (ref "J10")
      (value "PJ301_THONKICONN6")
      (footprint "eagle-import:WQP_PJ_301M6")
      (libsource (lib "eagle-import") (part "PJ301_THONKICONN6"))
    )
    (comp (ref "J11")
      (value "PJ301_THONKICONN6")
      (footprint "eagle-import:WQP_PJ_301M6")
      (libsource (lib "eagle-import") (part "PJ301_THONKICONN6"))
    )
    (comp (ref "J12")
      (value "PJ301_THONKICONN6")
      (footprint "eagle-import:WQP_PJ_301M6")
      (libsource (lib "eagle-import") (part "PJ301_THONKICONN6"))
    )
    (comp (ref "Q2")
      (value "MMBT3904")
      (footprint "eagle-import:SOT23-BEC")
      (libsource (lib "eagle-import") (part "-NPN-SOT23-BECMMBT3904LT1"))
    )
    (comp (ref "Q3")
      (value "MMBT3904")
      (footprint "eagle-import:SOT23-BEC")
      (libsource (lib "eagle-import") (part "-NPN-SOT23-BECMMBT3904LT1"))
    )
    (comp (ref "Q4")
      (value "MMBT3904")
      (footprint "eagle-import:SOT23-BEC")
      (libsource (lib "eagle-import") (part "-NPN-SOT23-BECMMBT3904LT1"))
    )
    (comp (ref "Q5")
      (value "MMBT3904")
      (footprint "eagle-import:SOT23-BEC")
      (libsource (lib "eagle-import") (part "-NPN-SOT23-BECMMBT3904LT1"))
    )
    (comp (ref "Q6")
      (value "MMBT3904")
      (footprint "eagle-import:SOT23-BEC")
      (libsource (lib "eagle-import") (part "-NPN-SOT23-BECMMBT3904LT1"))
    )
    (comp (ref "Q7")
      (value "MMBT3904")
      (footprint "eagle-import:SOT23-BEC")
      (libsource (lib "eagle-import") (part "-NPN-SOT23-BECMMBT3904LT1"))
    )
    (comp (ref "R60")
      (value "10k")
      (footprint "eagle-import:R0402")
      (libsource (lib "eagle-import") (part "R-US_R0402"))
    )
    (comp (ref "R61")
      (value "10k")
      (footprint "eagle-import:R0402")
      (libsource (lib "eagle-import") (part "R-US_R0402"))
    )
    (comp (ref "R62")
      (value "10k")
      (footprint "eagle-import:R0402")
      (libsource (lib "eagle-import") (part "R-US_R0402"))
    )
    (comp (ref "R63")
      (value "10k")
      (footprint "eagle-import:R0402")
      (libsource (lib "eagle-import") (part "R-US_R0402"))
    )
    (comp (ref "R64")
      (value "10k")
      (footprint "eagle-import:R0402")
      (libsource (lib "eagle-import") (part "R-US_R0402"))
    )
    (comp (ref "R65")
      (value "10k")
      (footprint "eagle-import:R0402")
      (libsource (lib "eagle-import") (part "R-US_R0402"))
    )
    (comp (ref "R66")
      (value "100k")
      (footprint "eagle-import:R0402")
      (libsource (lib "eagle-import") (part "R-US_R0402"))
    )
    (comp (ref "R67")
      (value "100k")
      (footprint "eagle-import:R0402")
      (libsource (lib "eagle-import") (part "R-US_R0402"))
    )
    (comp (ref "R68")
      (value "100k")
      (footprint "eagle-import:R0402")
      (libsource (lib "eagle-import") (part "R-US_R0402"))
    )
    (comp (ref "R69")
      (value "100k")
      (footprint "eagle-import:R0402")
      (libsource (lib "eagle-import") (part "R-US_R0402"))
    )
    (comp (ref "R70")
      (value "100k")
      (footprint "eagle-import:R0402")
      (libsource (lib "eagle-import") (part "R-US_R0402"))
    )
    (comp (ref "R71")
      (value "100k")
      (footprint "eagle-import:R0402")
      (libsource (lib "eagle-import") (part "R-US_R0402"))
    )
    (comp (ref "R72")
      (value "100k")
      (footprint "eagle-import:R0402")
      (libsource (lib "eagle-import") (part "R-US_R0402"))
    )
    (comp (ref "R73")
      (value "100k")
      (footprint "eagle-import:R0402")
      (libsource (lib "eagle-import") (part "R-US_R0402"))
    )
    (comp (ref "R74")
      (value "100k")
      (footprint "eagle-import:R0402")
      (libsource (lib "eagle-import") (part "R-US_R0402"))
    )
    (comp (ref "R75")
      (value "100k")
      (footprint "eagle-import:R0402")
      (libsource (lib "eagle-import") (part "R-US_R0402"))
    )
    (comp (ref "R76")
      (value "100k")
      (footprint "eagle-import:R0402")
      (libsource (lib "eagle-import") (part "R-US_R0402"))
    )
    (comp (ref "R77")
      (value "100k")
      (footprint "eagle-import:R0402")
      (libsource (lib "eagle-import") (part "R-US_R0402"))
    )
    (comp (ref "C5")
      (value "22u")
      (footprint "eagle-import:C1206")
      (libsource (lib "eagle-import") (part "C-USC1206"))
    )
    (comp (ref "C6")
      (value "22u")
      (footprint "eagle-import:C1206")
      (libsource (lib "eagle-import") (part "C-USC1206"))
    )
    (comp (ref "C7")
      (value "100n")
      (footprint "eagle-import:C0402")
      (libsource (lib "eagle-import") (part "C-USC0402"))
    )
    (comp (ref "C8")
      (value "100n")
      (footprint "eagle-import:C0402")
      (libsource (lib "eagle-import") (part "C-USC0402"))
    )
    (comp (ref "C16")
      (value "100n")
      (footprint "eagle-import:C0402")
      (libsource (lib "eagle-import") (part "C-USC0402"))
    )
    (comp (ref "H1")
      (value "MOUNT-HOLE3.0")
      (footprint "eagle-import:3,0")
      (libsource (lib "eagle-import") (part "MOUNT-HOLE3.0"))
    )
    (comp (ref "H2")
      (value "MOUNT-HOLE3.0")
      (footprint "eagle-import:3,0")
      (libsource (lib "eagle-import") (part "MOUNT-HOLE3.0"))
    )
    (comp (ref "IC1")
      (value "TLC59281DBQ")
      (footprint "eagle-import:TSSOP24_0635")
      (libsource (lib "eagle-import") (part "TLC59281DBQ"))
    )
    (comp (ref "IC3")
      (value "4051PW")
      (footprint "eagle-import:TSSOP16_065")
      (libsource (lib "eagle-import") (part "4051PW"))
    )
    (comp (ref "IC6")
      (value "4051PW")
      (footprint "eagle-import:TSSOP16_065")
      (libsource (lib "eagle-import") (part "4051PW"))
    )
    (comp (ref "JP1")
      (value "FIDUCIAL1X2")
      (footprint "eagle-import:FIDUCIAL-1X2")
      (libsource (lib "eagle-import") (part "FIDUCIAL1X2"))
    )
    (comp (ref "JP2")
      (value "FIDUCIAL1X2")
      (footprint "eagle-import:FIDUCIAL-1X2")
      (libsource (lib "eagle-import") (part "FIDUCIAL1X2"))
    )
    (comp (ref "JP7")
      (value "FIDUCIAL1X2")
      (footprint "eagle-import:FIDUCIAL-1X2")
      (libsource (lib "eagle-import") (part "FIDUCIAL1X2"))
    )
    (comp (ref "JP8")
      (value "FIDUCIAL1X2")
      (footprint "eagle-import:FIDUCIAL-1X2")
      (libsource (lib "eagle-import") (part "FIDUCIAL1X2"))
    )
    (comp (ref "L2")
      (value "WE-CBF_0603")
      (footprint "eagle-import:0603")
      (libsource (lib "eagle-import") (part "WE-CBF_0603"))
    )
    (comp (ref "LED7")
      (value "SSL-LX3059IGW-CA")
      (footprint "eagle-import:LED-BICOLOR-THROUGHHOLE-LUMEX")
      (libsource (lib "eagle-import") (part "LED-BICOLOR-THROUGHHOLE-CA"))
    )
    (comp (ref "LED8")
      (value "SSL-LX3059IGW-CA")
      (footprint "eagle-import:LED-BICOLOR-THROUGHHOLE-LUMEX")
      (libsource (lib "eagle-import") (part "LED-BICOLOR-THROUGHHOLE-CA"))
    )
    (comp (ref "LED9")
      (value "SSL-LX3059IGW-CA")
      (footprint "eagle-import:LED-BICOLOR-THROUGHHOLE-LUMEX")
      (libsource (lib "eagle-import") (part "LED-BICOLOR-THROUGHHOLE-CA"))
    )
    (comp (ref "LED10")
      (value "SSL-LX3059IGW-CA")
      (footprint "eagle-import:LED-BICOLOR-THROUGHHOLE-LUMEX")
      (libsource (lib "eagle-import") (part "LED-BICOLOR-THROUGHHOLE-CA"))
    )
    (comp (ref "LED11")
      (value "SSL-LX3059IGW-CA")
      (footprint "eagle-import:LED-BICOLOR-THROUGHHOLE-LUMEX")
      (libsource (lib "eagle-import") (part "LED-BICOLOR-THROUGHHOLE-CA"))
    )
    (comp (ref "LED12")
      (value "SSL-LX3059IGW-CA")
      (footprint "eagle-import:LED-BICOLOR-THROUGHHOLE-LUMEX")
      (libsource (lib "eagle-import") (part "LED-BICOLOR-THROUGHHOLE-CA"))
    )
    (comp (ref "R1")
      (value "15k")
      (footprint "eagle-import:R0402")
      (libsource (lib "eagle-import") (part "R-US_R0402"))
    )
    (comp (ref "R2")
      (value "15k")
      (footprint "eagle-import:R0402")
      (libsource (lib "eagle-import") (part "R-US_R0402"))
    )
    (comp (ref "R3")
      (value "15k")
      (footprint "eagle-import:R0402")
      (libsource (lib "eagle-import") (part "R-US_R0402"))
    )
    (comp (ref "R4")
      (value "15k")
      (footprint "eagle-import:R0402")
      (libsource (lib "eagle-import") (part "R-US_R0402"))
    )
    (comp (ref "R6")
      (value "10k")
      (footprint "eagle-import:R0402")
      (libsource (lib "eagle-import") (part "R-US_R0402"))
    )
    (comp (ref "R17")
      (value "15k")
      (footprint "eagle-import:R0402")
      (libsource (lib "eagle-import") (part "R-US_R0402"))
    )
    (comp (ref "R18")
      (value "15k")
      (footprint "eagle-import:R0402")
      (libsource (lib "eagle-import") (part "R-US_R0402"))
    )
    (comp (ref "R78")
      (value "20kB")
      (footprint "eagle-import:BOURNS_SLIDER")
      (libsource (lib "eagle-import") (part "BOURNS_SLIDER"))
    )
    (comp (ref "R79")
      (value "20kB")
      (footprint "eagle-import:BOURNS_SLIDER")
      (libsource (lib "eagle-import") (part "BOURNS_SLIDER"))
    )
    (comp (ref "R80")
      (value "20kB")
      (footprint "eagle-import:BOURNS_SLIDER")
      (libsource (lib "eagle-import") (part "BOURNS_SLIDER"))
    )
    (comp (ref "R81")
      (value "20kB")
      (footprint "eagle-import:BOURNS_SLIDER")
      (libsource (lib "eagle-import") (part "BOURNS_SLIDER"))
    )
    (comp (ref "R82")
      (value "20kB")
      (footprint "eagle-import:BOURNS_SLIDER")
      (libsource (lib "eagle-import") (part "BOURNS_SLIDER"))
    )
    (comp (ref "R83")
      (value "20kB")
      (footprint "eagle-import:BOURNS_SLIDER")
      (libsource (lib "eagle-import") (part "BOURNS_SLIDER"))
    )
    (comp (ref "R84")
      (value "10kB")
      (footprint "eagle-import:ALPS_POT_NARROW")
      (libsource (lib "eagle-import") (part "POT_USVERTICAL_NARROW"))
    )
    (comp (ref "R85")
      (value "10kB")
      (footprint "eagle-import:ALPS_POT_NARROW")
      (libsource (lib "eagle-import") (part "POT_USVERTICAL_NARROW"))
    )
    (comp (ref "R86")
      (value "10kB")
      (footprint "eagle-import:ALPS_POT_NARROW")
      (libsource (lib "eagle-import") (part "POT_USVERTICAL_NARROW"))
    )
    (comp (ref "R87")
      (value "10kB")
      (footprint "eagle-import:ALPS_POT_NARROW")
      (libsource (lib "eagle-import") (part "POT_USVERTICAL_NARROW"))
    )
    (comp (ref "R88")
      (value "10kB")
      (footprint "eagle-import:ALPS_POT_NARROW")
      (libsource (lib "eagle-import") (part "POT_USVERTICAL_NARROW"))
    )
    (comp (ref "R89")
      (value "10kB")
      (footprint "eagle-import:ALPS_POT_NARROW")
      (libsource (lib "eagle-import") (part "POT_USVERTICAL_NARROW"))
    )
    (comp (ref "SW1")
      (value "TAC_SWITCHPTH")
      (footprint "eagle-import:TACTILE-PTH")
      (libsource (lib "eagle-import") (part "TAC_SWITCHPTH"))
    )
    (comp (ref "SW2")
      (value "TAC_SWITCHPTH")
      (footprint "eagle-import:TACTILE-PTH")
      (libsource (lib "eagle-import") (part "TAC_SWITCHPTH"))
    )
    (comp (ref "SW3")
      (value "TAC_SWITCHPTH")
      (footprint "eagle-import:TACTILE-PTH")
      (libsource (lib "eagle-import") (part "TAC_SWITCHPTH"))
    )
    (comp (ref "SW4")
      (value "TAC_SWITCHPTH")
      (footprint "eagle-import:TACTILE-PTH")
      (libsource (lib "eagle-import") (part "TAC_SWITCHPTH"))
    )
    (comp (ref "SW5")
      (value "TAC_SWITCHPTH")
      (footprint "eagle-import:TACTILE-PTH")
      (libsource (lib "eagle-import") (part "TAC_SWITCHPTH"))
    )
    (comp (ref "SW6")
      (value "TAC_SWITCHPTH")
      (footprint "eagle-import:TACTILE-PTH")
      (libsource (lib "eagle-import") (part "TAC_SWITCHPTH"))
    )
    (comp (ref "C1")
      (value "22u")
      (footprint "eagle-import:C1206")
      (libsource (lib "eagle-import") (part "C-USC1206"))
    )
    (comp (ref "C2")
      (value "22u")
      (footprint "eagle-import:C1206")
      (libsource (lib "eagle-import") (part "C-USC1206"))
    )
    (comp (ref "C10")
      (value "22u")
      (footprint "eagle-import:C1206")
      (libsource (lib "eagle-import") (part "C-USC1206"))
    )
    (comp (ref "C15")
      (value "100n")
      (footprint "eagle-import:C0402")
      (libsource (lib "eagle-import") (part "C-USC0402"))
    )
    (comp (ref "C17")
      (value "22u")
      (footprint "eagle-import:C1206")
      (libsource (lib "eagle-import") (part "C-USC1206"))
    )
    (comp (ref "C19")
      (value "22u")
      (footprint "eagle-import:C1206")
      (libsource (lib "eagle-import") (part "C-USC1206"))
    )
    (comp (ref "C20")
      (value "22u")
      (footprint "eagle-import:C1206")
      (libsource (lib "eagle-import") (part "C-USC1206"))
    )
    (comp (ref "C21")
      (value "22u")
      (footprint "eagle-import:C1206")
      (libsource (lib "eagle-import") (part "C-USC1206"))
    )
    (comp (ref "C23")
      (value "22u")
      (footprint "eagle-import:C1206")
      (libsource (lib "eagle-import") (part "C-USC1206"))
    )
    (comp (ref "C25")
      (value "22u")
      (footprint "eagle-import:C1206")
      (libsource (lib "eagle-import") (part "C-USC1206"))
    )
    (comp (ref "C41")
      (value "1u")
      (footprint "eagle-import:C0402")
      (libsource (lib "eagle-import") (part "C-USC0402"))
    )
    (comp (ref "D1")
      (value "1N5819HW")
      (footprint "eagle-import:SOD123")
      (libsource (lib "eagle-import") (part "DIODE-SOD123"))
    )
    (comp (ref "D2")
      (value "1N5819HW")
      (footprint "eagle-import:SOD123")
      (libsource (lib "eagle-import") (part "DIODE-SOD123"))
    )
    (comp (ref "H3")
      (value "MOUNT-HOLE3.0TINY")
      (footprint "eagle-import:3,0TINY")
      (libsource (lib "eagle-import") (part "MOUNT-HOLE3.0TINY"))
    )
    (comp (ref "IC2")
      (value "ROF-78E3.3-0.5SMD")
      (footprint "eagle-import:ROF78EXX-0.5SMD")
      (libsource (lib "eagle-import") (part "ROF-78EXX-0.55SMD"))
    )
    (comp (ref "IC7")
      (value "LD2981ABU33")
      (footprint "eagle-import:SOT89")
      (libsource (lib "eagle-import") (part "LD2981ABU"))
    )
    (comp (ref "IC11")
      (value "LM4040B25")
      (footprint "eagle-import:DBZ_R-PDSO-G3")
      (libsource (lib "eagle-import") (part "LM4041DBZB12"))
    )
    (comp (ref "JP5")
      (value "M05X2SMD")
      (footprint "eagle-import:2X5-SMD")
      (libsource (lib "eagle-import") (part "M05X2SMD"))
    )
    (comp (ref "L1")
      (value "WE-CBF_0603")
      (footprint "eagle-import:0603")
      (libsource (lib "eagle-import") (part "WE-CBF_0603"))
    )
    (comp (ref "L3")
      (value "33u")
      (footprint "eagle-import:L2012C")
      (libsource (lib "eagle-import") (part "L-USL2012C"))
    )
    (comp (ref "L4")
      (value "WE-CBF_0603")
      (footprint "eagle-import:0603")
      (libsource (lib "eagle-import") (part "WE-CBF_0603"))
    )
    (comp (ref "L5")
      (value "WE-CBF_0603")
      (footprint "eagle-import:0603")
      (libsource (lib "eagle-import") (part "WE-CBF_0603"))
    )
    (comp (ref "R33")
      (value "10k")
      (footprint "eagle-import:R0402")
      (libsource (lib "eagle-import") (part "R-US_R0402"))
    )
  )
  (nets
    (net (code "1") (name "+3V3") (class "Default")
      (node (ref "C10") (pin "1") (pinfunction "1_1") (pintype "passive"))
      (node (ref "C11") (pin "1") (pinfunction "1_1") (pintype "passive"))
      (node (ref "C14") (pin "1") (pinfunction "1_1") (pintype "passive"))
      (node (ref "C15") (pin "1") (pinfunction "1_1") (pintype "passive"))
      (node (ref "C9") (pin "1") (pinfunction "1_1") (pintype "passive"))
      (node (ref "D9") (pin "2") (pinfunction "C_2") (pintype "passive"))
      (node (ref "IC2") (pin "3") (pinfunction "VO_3") (pintype "passive"))
      (node (ref "IC5") (pin "1") (pinfunction "VBAT_1") (pintype "power_in"))
      (node (ref "IC5") (pin "19") (pinfunction "VDD_2_19") (pintype "power_in"))
      (node (ref "IC5") (pin "64") (pinfunction "VDD_1_64") (pintype "power_in"))
      (node (ref "L2") (pin "2") (pinfunction "2_2") (pintype "passive"))
      (node (ref "LED10") (pin "A") (pinfunction "A_A") (pintype "bidirectional"))
      (node (ref "LED11") (pin "A") (pinfunction "A_A") (pintype "bidirectional"))
      (node (ref "LED12") (pin "A") (pinfunction "A_A") (pintype "bidirectional"))
      (node (ref "LED7") (pin "A") (pinfunction "A_A") (pintype "bidirectional"))
      (node (ref "LED8") (pin "A") (pinfunction "A_A") (pintype "bidirectional"))
      (node (ref "LED9") (pin "A") (pinfunction "A_A") (pintype "bidirectional"))
      (node (ref "R12") (pin "2") (pinfunction "2_2") (pintype "passive"))
    )
    (net (code "2") (name "+3V3_A") (class "Default")
      (node (ref "C12") (pin "1") (pinfunction "1_1") (pintype "passive"))
      (node (ref "C13") (pin "1") (pinfunction "1_1") (pintype "passive"))
      (node (ref "C16") (pin "1") (pinfunction "1_1") (pintype "passive"))
      (node (ref "C18") (pin "1") (pinfunction "1_1") (pintype "passive"))
      (node (ref "C20") (pin "1") (pinfunction "1_1") (pintype "passive"))
      (node (ref "C22") (pin "1") (pinfunction "1_1") (pintype "passive"))
      (node (ref "C24") (pin "1") (pinfunction "1_1") (pintype "passive"))
      (node (ref "C26") (pin "1") (pinfunction "1_1") (pintype "passive"))
      (node (ref "C30") (pin "1") (pinfunction "1_1") (pintype "passive"))
      (node (ref "C33") (pin "1") (pinfunction "1_1") (pintype "passive"))
      (node (ref "C34") (pin "1") (pinfunction "1_1") (pintype "passive"))
      (node (ref "C5") (pin "1") (pinfunction "1_1") (pintype "passive"))
      (node (ref "C7") (pin "1") (pinfunction "1_1") (pintype "passive"))
      (node (ref "IC10") (pin "8") (pinfunction "V+_8") (pintype "power_in"))
      (node (ref "IC3") (pin "16") (pinfunction "VCC_16") (pintype "power_in"))
      (node (ref "IC4") (pin "2") (pinfunction "AVDD_2") (pintype "power_in"))
      (node (ref "IC5") (pin "13") (pinfunction "VDDA_13") (pintype "power_in"))
      (node (ref "IC5") (pin "17") (pinfunction "VREF+_17") (pintype "power_in"))
      (node (ref "IC5") (pin "32") (pinfunction "VDDSD_32") (pintype "power_in"))
      (node (ref "IC5") (pin "33") (pinfunction "VREFSD+_33") (pintype "power_in"))
      (node (ref "IC6") (pin "16") (pinfunction "VCC_16") (pintype "power_in"))
      (node (ref "IC7") (pin "1") (pinfunction "VO_1") (pintype "passive"))
      (node (ref "IC8") (pin "8") (pinfunction "V+_8") (pintype "power_in"))
      (node (ref "IC9") (pin "8") (pinfunction "V+_8") (pintype "power_in"))
      (node (ref "R78") (pin "3") (pinfunction "E_3") (pintype "passive"))
      (node (ref "R79") (pin "3") (pinfunction "E_3") (pintype "passive"))
      (node (ref "R80") (pin "3") (pinfunction "E_3") (pintype "passive"))
      (node (ref "R81") (pin "3") (pinfunction "E_3") (pintype "passive"))
      (node (ref "R82") (pin "3") (pinfunction "E_3") (pintype "passive"))
      (node (ref "R83") (pin "3") (pinfunction "E_3") (pintype "passive"))
      (node (ref "R84") (pin "P$1") (pinfunction "E_P$1") (pintype "passive"))
      (node (ref "R85") (pin "P$1") (pinfunction "E_P$1") (pintype "passive"))
      (node (ref "R86") (pin "P$1") (pinfunction "E_P$1") (pintype "passive"))
      (node (ref "R87") (pin "P$1") (pinfunction "E_P$1") (pintype "passive"))
      (node (ref "R88") (pin "P$1") (pinfunction "E_P$1") (pintype "passive"))
      (node (ref "R89") (pin "P$1") (pinfunction "E_P$1") (pintype "passive"))
    )
    (net (code "3") (name "ADC_CV_1") (class "Default")
      (node (ref "C35") (pin "2") (pinfunction "2_2") (pintype "passive"))
      (node (ref "IC10") (pin "7") (pinfunction "OUT_7") (pintype "output"))
      (node (ref "IC5") (pin "34") (pinfunction "PB14/SPI2_MISO/I2S2_MCK/USART3_RTS/SDADC3_AIN8P_34") (pintype "bidirectional"))
      (node (ref "R16") (pin "1") (pinfunction "1_1") (pintype "passive"))
    )
    (net (code "4") (name "ADC_CV_2") (class "Default")
      (node (ref "C32") (pin "2") (pinfunction "2_2") (pintype "passive"))
      (node (ref "IC10") (pin "1") (pinfunction "OUT_1") (pintype "output"))
      (node (ref "IC5") (pin "35") (pinfunction "PB15/SPI2_MOSI/I2S2_SD/SDADC3_AIN7P/SDADC3_AIN8M_35") (pintype "bidirectional"))
      (node (ref "R14") (pin "1") (pinfunction "1_1") (pintype "passive"))
    )
    (net (code "5") (name "ADC_CV_3") (class "Default")
      (node (ref "C31") (pin "2") (pinfunction "2_2") (pintype "passive"))
      (node (ref "IC5") (pin "29") (pinfunction "PE8/SDADC1_AIN8P/SDADC2_AIN8P_29") (pintype "bidirectional"))
      (node (ref "IC9") (pin "7") (pinfunction "OUT_7") (pintype "output"))
      (node (ref "R13") (pin "1") (pinfunction "1_1") (pintype "passive"))
    )
    (net (code "6") (name "ADC_CV_4") (class "Default")
      (node (ref "C29") (pin "2") (pinfunction "2_2") (pintype "passive"))
      (node (ref "IC5") (pin "30") (pinfunction "PE9/SDADC1_AIN7P/SDADC1_AIN8M/SDADC2_AIN7P/SDADC2_AIN8M_30") (pintype "bidirectional"))
      (node (ref "IC9") (pin "1") (pinfunction "OUT_1") (pintype "output"))
      (node (ref "R15") (pin "1") (pinfunction "1_1") (pintype "passive"))
    )
    (net (code "7") (name "ADC_CV_5") (class "Default")
      (node (ref "C27") (pin "2") (pinfunction "2_2") (pintype "passive"))
      (node (ref "IC5") (pin "27") (pinfunction "PB1/TIM3_CH4/ADC_IN9/SDADC1_AIN5P/SDADC1_AIN6M_27") (pintype "bidirectional"))
      (node (ref "IC8") (pin "7") (pinfunction "OUT_7") (pintype "output"))
      (node (ref "R19") (pin "1") (pinfunction "1_1") (pintype "passive"))
    )
    (net (code "8") (name "ADC_CV_6") (class "Default")
      (node (ref "C28") (pin "2") (pinfunction "2_2") (pintype "passive"))
      (node (ref "IC5") (pin "26") (pinfunction "PB0/SPI1_MOSI/I2S1_SD/TIM3_CH3/ADC_IN8/SDADC1_AIN6P_26") (pintype "bidirectional"))
      (node (ref "IC8") (pin "1") (pinfunction "OUT_1") (pintype "output"))
      (node (ref "R20") (pin "1") (pinfunction "1_1") (pintype "passive"))
    )
    (net (code "9") (name "ADC_SHAPE") (class "Default")
      (node (ref "IC3") (pin "3") (pinfunction "X_3") (pintype "bidirectional"))
      (node (ref "IC5") (pin "22") (pinfunction "PA6/SPI1_MISO/I2S1_MCK/TIM3_CH1/ADC_IN6/DAC2_OUT1_22") (pintype "bidirectional"))
    )
    (net (code "10") (name "ADC_TIME_LEVEL") (class "Default")
      (node (ref "IC5") (pin "23") (pinfunction "PA7/SPI1_MOSI/I2S1_SD/TIM3_CH2/ADC_IN7_23") (pintype "bidirectional"))
      (node (ref "IC6") (pin "3") (pinfunction "X_3") (pintype "bidirectional"))
    )
    (net (code "11") (name "AREF_-2.5") (class "Default")
      (node (ref "C41") (pin "1") (pinfunction "1_1") (pintype "passive"))
      (node (ref "IC11") (pin "2") (pinfunction "A_2") (pintype "passive"))
      (node (ref "R21") (pin "2") (pinfunction "2_2") (pintype "passive"))
      (node (ref "R22") (pin "2") (pinfunction "2_2") (pintype "passive"))
      (node (ref "R23") (pin "2") (pinfunction "2_2") (pintype "passive"))
      (node (ref "R24") (pin "2") (pinfunction "2_2") (pintype "passive"))
      (node (ref "R26") (pin "2") (pinfunction "2_2") (pintype "passive"))
      (node (ref "R29") (pin "2") (pinfunction "2_2") (pintype "passive"))
      (node (ref "R33") (pin "2") (pinfunction "2_2") (pintype "passive"))
    )
    (net (code "12") (name "AREF_2.5") (class "Default")
      (node (ref "IC4") (pin "7") (pinfunction "VREF_7") (pintype "input"))
      (node (ref "R40") (pin "2") (pinfunction "2_2") (pintype "passive"))
    )
    (net (code "13") (name "DAC_1") (class "Default")
      (node (ref "IC4") (pin "10") (pinfunction "VOUTD_10") (pintype "output"))
      (node (ref "R52") (pin "2") (pinfunction "2_2") (pintype "passive"))
    )
    (net (code "14") (name "DAC_2") (class "Default")
      (node (ref "IC4") (pin "11") (pinfunction "VOUTB_11") (pintype "output"))
      (node (ref "R51") (pin "2") (pinfunction "2_2") (pintype "passive"))
    )
    (net (code "15") (name "DAC_3") (class "Default")
      (node (ref "IC4") (pin "6") (pinfunction "VOUTG_6") (pintype "output"))
      (node (ref "R53") (pin "2") (pinfunction "2_2") (pintype "passive"))
    )
    (net (code "16") (name "DAC_4") (class "Default")
      (node (ref "IC4") (pin "4") (pinfunction "VOUTC_4") (pintype "output"))
      (node (ref "R49") (pin "2") (pinfunction "2_2") (pintype "passive"))
    )
    (net (code "17") (name "DAC_5") (class "Default")
      (node (ref "IC4") (pin "3") (pinfunction "VOUTA_3") (pintype "output"))
      (node (ref "R50") (pin "2") (pinfunction "2_2") (pintype "passive"))
    )
    (net (code "18") (name "DAC_6") (class "Default")
      (node (ref "IC4") (pin "5") (pinfunction "VOUTE_5") (pintype "output"))
      (node (ref "R47") (pin "2") (pinfunction "2_2") (pintype "passive"))
    )
    (net (code "19") (name "DAC_MOSI") (class "Default")
      (node (ref "IC4") (pin "13") (pinfunction "DIN_13") (pintype "input"))
      (node (ref "IC5") (pin "53") (pinfunction "PC12/SPI3_MOSI/I2S3_SD/USART3_CK_53") (pintype "bidirectional"))
    )
    (net (code "20") (name "DAC_SCK") (class "Default")
      (node (ref "IC4") (pin "14") (pinfunction "SCLK_14") (pintype "input"))
      (node (ref "IC5") (pin "51") (pinfunction "PC10/SPI3_SCK/I2S3_CK/USART3_TX_51") (pintype "bidirectional"))
    )
    (net (code "21") (name "DAC_SS") (class "Default")
      (node (ref "IC4") (pin "1") (pinfunction "~{SYNC}_1") (pintype "input"))
      (node (ref "IC5") (pin "50") (pinfunction "PA15/SPI1_NSS/I2S1_WS/SPI3_NSS/I2S3_WS/I2C1_SCL/TIM2_CH1_ETR/JTDI_50") (pintype "bidirectional"))
    )
    (net (code "22") (name "GATE_1") (class "Default")
      (node (ref "IC5") (pin "44") (pinfunction "PA11/SPI2_NSS/I2S2_WS/SPI1_NSS/I2S1_WS/USART1_CTS/CAN_RX/TIM4_CH1/TIM5_CH2_44") (pintype "bidirectional"))
      (node (ref "Q7") (pin "C") (pinfunction "C_C") (pintype "passive"))
    )
    (net (code "23") (name "GATE_2") (class "Default")
      (node (ref "IC5") (pin "43") (pinfunction "PA10/SPI2_MOSI/I2S2_SD/I2C2_SDA/USART1_RX/TIM2_CH4_43") (pintype "bidirectional"))
      (node (ref "Q3") (pin "C") (pinfunction "C_C") (pintype "passive"))
    )
    (net (code "24") (name "GATE_3") (class "Default")
      (node (ref "IC5") (pin "42") (pinfunction "PA9/SPI_MISO/I2S2_MCK/I2C2_SCL/USART1_TX/TIM2_CH3_42") (pintype "bidirectional"))
      (node (ref "Q6") (pin "C") (pinfunction "C_C") (pintype "passive"))
    )
    (net (code "25") (name "GATE_4") (class "Default")
      (node (ref "IC5") (pin "41") (pinfunction "PA8/SPI2_SCK/I2S2_CK/I2C2_SMBA/USART1_CK/TIM5_CH1_41") (pintype "bidirectional"))
      (node (ref "Q4") (pin "C") (pinfunction "C_C") (pintype "passive"))
    )
    (net (code "26") (name "GATE_5") (class "Default")
      (node (ref "IC5") (pin "39") (pinfunction "PC8/SPI1_MISO/I2S1_MCK/TIM3_CH3_39") (pintype "bidirectional"))
      (node (ref "Q5") (pin "C") (pinfunction "C_C") (pintype "passive"))
    )
    (net (code "27") (name "GATE_6") (class "Default")
      (node (ref "IC5") (pin "38") (pinfunction "PC7/SPI1_SCK/I2S1_CK/TIM3_CH2_38") (pintype "bidirectional"))
      (node (ref "Q2") (pin "C") (pinfunction "C_C") (pintype "passive"))
    )
    (net (code "28") (name "GND") (class "Default")
      (node (ref "C1") (pin "1") (pinfunction "1_1") (pintype "passive"))
      (node (ref "C10") (pin "2") (pinfunction "2_2") (pintype "passive"))
      (node (ref "C11") (pin "2") (pinfunction "2_2") (pintype "passive"))
      (node (ref "C12") (pin "2") (pinfunction "2_2") (pintype "passive"))
      (node (ref "C13") (pin "2") (pinfunction "2_2") (pintype "passive"))
      (node (ref "C14") (pin "2") (pinfunction "2_2") (pintype "passive"))
      (node (ref "C15") (pin "2") (pinfunction "2_2") (pintype "passive"))
      (node (ref "C16") (pin "2") (pinfunction "2_2") (pintype "passive"))
      (node (ref "C17") (pin "2") (pinfunction "2_2") (pintype "passive"))
      (node (ref "C18") (pin "2") (pinfunction "2_2") (pintype "passive"))
      (node (ref "C19") (pin "2") (pinfunction "2_2") (pintype "passive"))
      (node (ref "C2") (pin "1") (pinfunction "1_1") (pintype "passive"))
      (node (ref "C20") (pin "2") (pinfunction "2_2") (pintype "passive"))
      (node (ref "C21") (pin "2") (pinfunction "2_2") (pintype "passive"))
      (node (ref "C22") (pin "2") (pinfunction "2_2") (pintype "passive"))
      (node (ref "C23") (pin "2") (pinfunction "2_2") (pintype "passive"))
      (node (ref "C24") (pin "2") (pinfunction "2_2") (pintype "passive"))
      (node (ref "C25") (pin "2") (pinfunction "2_2") (pintype "passive"))
      (node (ref "C26") (pin "2") (pinfunction "2_2") (pintype "passive"))
      (node (ref "C3") (pin "1") (pinfunction "1_1") (pintype "passive"))
      (node (ref "C30") (pin "2") (pinfunction "2_2") (pintype "passive"))
      (node (ref "C33") (pin "2") (pinfunction "2_2") (pintype "passive"))
      (node (ref "C34") (pin "2") (pinfunction "2_2") (pintype "passive"))
      (node (ref "C36") (pin "2") (pinfunction "2_2") (pintype "passive"))
      (node (ref "C37") (pin "2") (pinfunction "2_2") (pintype "passive"))
      (node (ref "C38") (pin "2") (pinfunction "2_2") (pintype "passive"))
      (node (ref "C39") (pin "2") (pinfunction "2_2") (pintype "passive"))
      (node (ref "C4") (pin "1") (pinfunction "1_1") (pintype "passive"))
      (node (ref "C40") (pin "2") (pinfunction "2_2") (pintype "passive"))
      (node (ref "C41") (pin "2") (pinfunction "2_2") (pintype "passive"))
      (node (ref "C42") (pin "2") (pinfunction "2_2") (pintype "passive"))
      (node (ref "C43") (pin "2") (pinfunction "2_2") (pintype "passive"))
      (node (ref "C5") (pin "2") (pinfunction "2_2") (pintype "passive"))
      (node (ref "C50") (pin "2") (pinfunction "2_2") (pintype "passive"))
      (node (ref "C51") (pin "1") (pinfunction "1_1") (pintype "passive"))
      (node (ref "C52") (pin "2") (pinfunction "2_2") (pintype "passive"))
      (node (ref "C53") (pin "1") (pinfunction "1_1") (pintype "passive"))
      (node (ref "C54") (pin "2") (pinfunction "2_2") (pintype "passive"))
      (node (ref "C55") (pin "1") (pinfunction "1_1") (pintype "passive"))
      (node (ref "C6") (pin "2") (pinfunction "2_2") (pintype "passive"))
      (node (ref "C7") (pin "2") (pinfunction "2_2") (pintype "passive"))
      (node (ref "C8") (pin "2") (pinfunction "2_2") (pintype "passive"))
      (node (ref "C9") (pin "2") (pinfunction "2_2") (pintype "passive"))
      (node (ref "D3") (pin "A") (pinfunction "A_A") (pintype "passive"))
      (node (ref "D4") (pin "A") (pinfunction "A_A") (pintype "passive"))
      (node (ref "D5") (pin "A") (pinfunction "A_A") (pintype "passive"))
      (node (ref "D6") (pin "A") (pinfunction "A_A") (pintype "passive"))
      (node (ref "D7") (pin "A") (pinfunction "A_A") (pintype "passive"))
      (node (ref "D8") (pin "A") (pinfunction "A_A") (pintype "passive"))
      (node (ref "D9") (pin "1") (pinfunction "A_1") (pintype "passive"))
      (node (ref "IC1") (pin "1") (pinfunction "GND_1") (pintype "bidirectional"))
      (node (ref "IC1") (pin "21") (pinfunction "BLANK_21") (pintype "bidirectional"))
      (node (ref "IC10") (pin "3") (pinfunction "+IN_3") (pintype "input"))
      (node (ref "IC10") (pin "4") (pinfunction "V-_4") (pintype "power_in"))
      (node (ref "IC10") (pin "5") (pinfunction "+IN_5") (pintype "input"))
      (node (ref "IC11") (pin "1") (pinfunction "C_1") (pintype "passive"))
      (node (ref "IC2") (pin "2") (pinfunction "GND_2") (pintype "passive"))
      (node (ref "IC3") (pin "6") (pinfunction "INH_6") (pintype "input"))
      (node (ref "IC3") (pin "7") (pinfunction "VEE_7") (pintype "power_in"))
      (node (ref "IC3") (pin "8") (pinfunction "GND_8") (pintype "power_in"))
      (node (ref "IC4") (pin "12") (pinfunction "GND_12") (pintype "passive"))
      (node (ref "IC5") (pin "12") (pinfunction "VSSA_12") (pintype "power_in"))
      (node (ref "IC5") (pin "31") (pinfunction "VSSSD/VREFSD-_31") (pintype "power_in"))
      (node (ref "IC5") (pin "60") (pinfunction "BOOT0_60") (pintype "bidirectional"))
      (node (ref "IC5") (pin "63") (pinfunction "VSS_1_63") (pintype "power_in"))
      (node (ref "IC6") (pin "6") (pinfunction "INH_6") (pintype "input"))
      (node (ref "IC6") (pin "7") (pinfunction "VEE_7") (pintype "power_in"))
      (node (ref "IC6") (pin "8") (pinfunction "GND_8") (pintype "power_in"))
      (node (ref "IC7") (pin "2") (pinfunction "GND_2") (pintype "passive"))
      (node (ref "IC8") (pin "3") (pinfunction "+IN_3") (pintype "input"))
      (node (ref "IC8") (pin "4") (pinfunction "V-_4") (pintype "power_in"))
      (node (ref "IC8") (pin "5") (pinfunction "+IN_5") (pintype "input"))
      (node (ref "IC9") (pin "3") (pinfunction "+IN_3") (pintype "input"))
      (node (ref "IC9") (pin "4") (pinfunction "V-_4") (pintype "power_in"))
      (node (ref "IC9") (pin "5") (pinfunction "+IN_5") (pintype "input"))
      (node (ref "J1") (pin "P1") (pinfunction "1_P1") (pintype "passive"))
      (node (ref "J10") (pin "P1") (pinfunction "1_P1") (pintype "passive"))
      (node (ref "J11") (pin "P1") (pinfunction "1_P1") (pintype "passive"))
      (node (ref "J12") (pin "P1") (pinfunction "1_P1") (pintype "passive"))
      (node (ref "J13") (pin "P1") (pinfunction "1_P1") (pintype "passive"))
      (node (ref "J13") (pin "P2") (pinfunction "2_P2") (pintype "passive"))
      (node (ref "J14") (pin "P1") (pinfunction "1_P1") (pintype "passive"))
      (node (ref "J14") (pin "P2") (pinfunction "2_P2") (pintype "passive"))
      (node (ref "J15") (pin "P1") (pinfunction "1_P1") (pintype "passive"))
      (node (ref "J15") (pin "P2") (pinfunction "2_P2") (pintype "passive"))
      (node (ref "J16") (pin "P1") (pinfunction "1_P1") (pintype "passive"))
      (node (ref "J16") (pin "P2") (pinfunction "2_P2") (pintype "passive"))
      (node (ref "J17") (pin "P1") (pinfunction "1_P1") (pintype "passive"))
      (node (ref "J17") (pin "P2") (pinfunction "2_P2") (pintype "passive"))
      (node (ref "J18") (pin "P1") (pinfunction "1_P1") (pintype "passive"))
      (node (ref "J18") (pin "P2") (pinfunction "2_P2") (pintype "passive"))
      (node (ref "J2") (pin "P1") (pinfunction "1_P1") (pintype "passive"))
      (node (ref "J3") (pin "P1") (pinfunction "1_P1") (pintype "passive"))
      (node (ref "J4") (pin "P1") (pinfunction "1_P1") (pintype "passive"))
      (node (ref "J5") (pin "P1") (pinfunction "1_P1") (pintype "passive"))
      (node (ref "J6") (pin "P1") (pinfunction "1_P1") (pintype "passive"))
      (node (ref "J7") (pin "P1") (pinfunction "1_P1") (pintype "passive"))
      (node (ref "J8") (pin "P1") (pinfunction "1_P1") (pintype "passive"))
      (node (ref "J9") (pin "P1") (pinfunction "1_P1") (pintype "passive"))
      (node (ref "JP3") (pin "1") (pinfunction "1_1") (pintype "passive"))
      (node (ref "JP4") (pin "1") (pinfunction "1_1") (pintype "passive"))
      (node (ref "JP5") (pin "3") (pinfunction "3_3") (pintype "passive"))
      (node (ref "JP5") (pin "4") (pinfunction "4_4") (pintype "passive"))
      (node (ref "JP5") (pin "5") (pinfunction "5_5") (pintype "passive"))
      (node (ref "JP5") (pin "6") (pinfunction "6_6") (pintype "passive"))
      (node (ref "JP5") (pin "7") (pinfunction "7_7") (pintype "passive"))
      (node (ref "JP5") (pin "8") (pinfunction "8_8") (pintype "passive"))
      (node (ref "JP6") (pin "1") (pinfunction "1_1") (pintype "passive"))
      (node (ref "Q1") (pin "2") (pinfunction "LID1_2") (pintype "power_in"))
      (node (ref "Q1") (pin "4") (pinfunction "LID2_4") (pintype "power_in"))
      (node (ref "Q2") (pin "E") (pinfunction "E_E") (pintype "passive"))
      (node (ref "Q3") (pin "E") (pinfunction "E_E") (pintype "passive"))
      (node (ref "Q4") (pin "E") (pinfunction "E_E") (pintype "passive"))
      (node (ref "Q5") (pin "E") (pinfunction "E_E") (pintype "passive"))
      (node (ref "Q6") (pin "E") (pinfunction "E_E") (pintype "passive"))
      (node (ref "Q7") (pin "E") (pinfunction "E_E") (pintype "passive"))
      (node (ref "R48") (pin "1") (pinfunction "1_1") (pintype "passive"))
      (node (ref "R54") (pin "2") (pinfunction "2_2") (pintype "passive"))
      (node (ref "R55") (pin "2") (pinfunction "2_2") (pintype "passive"))
      (node (ref "R56") (pin "2") (pinfunction "2_2") (pintype "passive"))
      (node (ref "R57") (pin "2") (pinfunction "2_2") (pintype "passive"))
      (node (ref "R58") (pin "2") (pinfunction "2_2") (pintype "passive"))
      (node (ref "R59") (pin "2") (pinfunction "2_2") (pintype "passive"))
      (node (ref "R6") (pin "2") (pinfunction "2_2") (pintype "passive"))
      (node (ref "R69") (pin "1") (pinfunction "1_1") (pintype "passive"))
      (node (ref "R70") (pin "1") (pinfunction "1_1") (pintype "passive"))
      (node (ref "R71") (pin "1") (pinfunction "1_1") (pintype "passive"))
      (node (ref "R72") (pin "1") (pinfunction "1_1") (pintype "passive"))
      (node (ref "R73") (pin "1") (pinfunction "1_1") (pintype "passive"))
      (node (ref "R74") (pin "1") (pinfunction "1_1") (pintype "passive"))
      (node (ref "R78") (pin "1") (pinfunction "A_1") (pintype "passive"))
      (node (ref "R78") (pin "E") (pinfunction "C_E") (pintype "passive"))
      (node (ref "R79") (pin "1") (pinfunction "A_1") (pintype "passive"))
      (node (ref "R79") (pin "E") (pinfunction "C_E") (pintype "passive"))
      (node (ref "R80") (pin "1") (pinfunction "A_1") (pintype "passive"))
      (node (ref "R80") (pin "E") (pinfunction "C_E") (pintype "passive"))
      (node (ref "R81") (pin "1") (pinfunction "A_1") (pintype "passive"))
      (node (ref "R81") (pin "E") (pinfunction "C_E") (pintype "passive"))
      (node (ref "R82") (pin "1") (pinfunction "A_1") (pintype "passive"))
      (node (ref "R82") (pin "E") (pinfunction "C_E") (pintype "passive"))
      (node (ref "R83") (pin "1") (pinfunction "A_1") (pintype "passive"))
      (node (ref "R83") (pin "E") (pinfunction "C_E") (pintype "passive"))
      (node (ref "R84") (pin "P$3") (pinfunction "A_P$3") (pintype "passive"))
      (node (ref "R85") (pin "P$3") (pinfunction "A_P$3") (pintype "passive"))
      (node (ref "R86") (pin "P$3") (pinfunction "A_P$3") (pintype "passive"))
      (node (ref "R87") (pin "P$3") (pinfunction "A_P$3") (pintype "passive"))
      (node (ref "R88") (pin "P$3") (pinfunction "A_P$3") (pintype "passive"))
      (node (ref "R89") (pin "P$3") (pinfunction "A_P$3") (pintype "passive"))
      (node (ref "SW1") (pin "1") (pinfunction "1_1") (pintype "passive"))
      (node (ref "SW1") (pin "2") (pinfunction "2_2") (pintype "passive"))
      (node (ref "SW2") (pin "1") (pinfunction "1_1") (pintype "passive"))
      (node (ref "SW2") (pin "2") (pinfunction "2_2") (pintype "passive"))
      (node (ref "SW3") (pin "1") (pinfunction "1_1") (pintype "passive"))
      (node (ref "SW3") (pin "2") (pinfunction "2_2") (pintype "passive"))
      (node (ref "SW4") (pin "1") (pinfunction "1_1") (pintype "passive"))
      (node (ref "SW4") (pin "2") (pinfunction "2_2") (pintype "passive"))
      (node (ref "SW5") (pin "1") (pinfunction "1_1") (pintype "passive"))
      (node (ref "SW5") (pin "2") (pinfunction "2_2") (pintype "passive"))
      (node (ref "SW6") (pin "1") (pinfunction "1_1") (pintype "passive"))
      (node (ref "SW6") (pin "2") (pinfunction "2_2") (pintype "passive"))
    )
    (net (code "29") (name "LEDS_SCK") (class "Default")
      (node (ref "IC1") (pin "3") (pinfunction "SCLK_3") (pintype "bidirectional"))
      (node (ref "IC5") (pin "58") (pinfunction "PB6/I2C1_SCL/USART1_TX/TIM4_CH1_58") (pintype "bidirectional"))
    )
    (net (code "30") (name "LEDS_SIN") (class "Default")
      (node (ref "IC1") (pin "2") (pinfunction "SIN_2") (pintype "bidirectional"))
      (node (ref "IC5") (pin "57") (pinfunction "PB5/SPI1_MOSI/I2S1_SD/SPI3_MOSI/I2S3_SD/I2C1_SMBAI/USART2_CK/TIM3_CH2_57") (pintype "bidirectional"))
    )
    (net (code "31") (name "LEDS_SS") (class "Default")
      (node (ref "IC1") (pin "4") (pinfunction "LAT_4") (pintype "bidirectional"))
      (node (ref "IC5") (pin "59") (pinfunction "PB7/I2C1_SDA/USART1_RX/TIM4_CH2_59") (pintype "bidirectional"))
    )
    (net (code "32") (name "LEFT_RX") (class "Default")
      (node (ref "IC5") (pin "62") (pinfunction "PB9/SPI2_NSS/I2S2_WS/I2C1_SDA/USART3_RX/CAN_TX/TIM4_CH4_62") (pintype "bidirectional"))
      (node (ref "R7") (pin "1") (pinfunction "1_1") (pintype "passive"))
    )
    (net (code "33") (name "LEFT_TX") (class "Default")
      (node (ref "IC5") (pin "61") (pinfunction "PB8/SPI2_SCK/I2S2_CK/I2C1_SCL/USART3_TX/CAN_RX/TIM4_CH3_61") (pintype "bidirectional"))
      (node (ref "R5") (pin "1") (pinfunction "1_1") (pintype "passive"))
    )
    (net (code "34") (name "NORMALIZATION_PROBE") (class "Default")
      (node (ref "D9") (pin "3") (pinfunction "AC_3") (pintype "passive"))
      (node (ref "IC5") (pin "40") (pinfunction "PC9/SPI1_MOSI/I2S1_SD/TIM3_CH4_40") (pintype "bidirectional"))
      (node (ref "R60") (pin "1") (pinfunction "1_1") (pintype "passive"))
      (node (ref "R61") (pin "1") (pinfunction "1_1") (pintype "passive"))
      (node (ref "R62") (pin "1") (pinfunction "1_1") (pintype "passive"))
      (node (ref "R63") (pin "1") (pinfunction "1_1") (pintype "passive"))
      (node (ref "R64") (pin "1") (pinfunction "1_1") (pintype "passive"))
      (node (ref "R65") (pin "1") (pinfunction "1_1") (pintype "passive"))
    )
    (net (code "35") (name "Net-(C3-Pad2)") (class "Default")
      (node (ref "C3") (pin "2") (pinfunction "2_2") (pintype "passive"))
      (node (ref "Q1") (pin "1") (pinfunction "1_1") (pintype "passive"))
      (node (ref "R9") (pin "2") (pinfunction "2_2") (pintype "passive"))
    )
    (net (code "36") (name "Net-(C17-Pad1)") (class "Default")
      (node (ref "C17") (pin "1") (pinfunction "1_1") (pintype "passive"))
      (node (ref "D2") (pin "C") (pinfunction "C_C") (pintype "passive"))
      (node (ref "L3") (pin "1") (pinfunction "1_1") (pintype "passive"))
      (node (ref "L4") (pin "2") (pinfunction "2_2") (pintype "passive"))
      (node (ref "L5") (pin "2") (pinfunction "2_2") (pintype "passive"))
    )
    (net (code "37") (name "Net-(D1-PadA)") (class "Default")
      (node (ref "D1") (pin "A") (pinfunction "A_A") (pintype "passive"))
      (node (ref "L1") (pin "2") (pinfunction "2_2") (pintype "passive"))
    )
    (net (code "38") (name "Net-(D1-PadC)") (class "Default")
      (node (ref "D1") (pin "C") (pinfunction "C_C") (pintype "passive"))
      (node (ref "JP5") (pin "10") (pinfunction "10_10") (pintype "passive"))
      (node (ref "JP5") (pin "9") (pinfunction "9_9") (pintype "passive"))
    )
    (net (code "39") (name "Net-(D2-PadA)") (class "Default")
      (node (ref "D2") (pin "A") (pinfunction "A_A") (pintype "passive"))
      (node (ref "JP5") (pin "1") (pinfunction "1_1") (pintype "passive"))
      (node (ref "JP5") (pin "2") (pinfunction "2_2") (pintype "passive"))
    )
    (net (code "40") (name "Net-(D3-PadC)") (class "Default")
      (node (ref "D3") (pin "C") (pinfunction "C_C") (pintype "passive"))
      (node (ref "Q7") (pin "B") (pinfunction "B_B") (pintype "passive"))
      (node (ref "R66") (pin "2") (pinfunction "2_2") (pintype "passive"))
      (node (ref "R69") (pin "2") (pinfunction "2_2") (pintype "passive"))
    )
    (net (code "41") (name "Net-(D4-PadC)") (class "Default")
      (node (ref "D4") (pin "C") (pinfunction "C_C") (pintype "passive"))
      (node (ref "Q5") (pin "B") (pinfunction "B_B") (pintype "passive"))
      (node (ref "R67") (pin "2") (pinfunction "2_2") (pintype "passive"))
      (node (ref "R70") (pin "2") (pinfunction "2_2") (pintype "passive"))
    )
    (net (code "42") (name "Net-(D5-PadC)") (class "Default")
      (node (ref "D5") (pin "C") (pinfunction "C_C") (pintype "passive"))
      (node (ref "Q6") (pin "B") (pinfunction "B_B") (pintype "passive"))
      (node (ref "R68") (pin "2") (pinfunction "2_2") (pintype "passive"))
      (node (ref "R71") (pin "2") (pinfunction "2_2") (pintype "passive"))
    )
    (net (code "43") (name "Net-(D6-PadC)") (class "Default")
      (node (ref "D6") (pin "C") (pinfunction "C_C") (pintype "passive"))
      (node (ref "Q2") (pin "B") (pinfunction "B_B") (pintype "passive"))
      (node (ref "R74") (pin "2") (pinfunction "2_2") (pintype "passive"))
      (node (ref "R75") (pin "2") (pinfunction "2_2") (pintype "passive"))
    )
    (net (code "44") (name "Net-(D7-PadC)") (class "Default")
      (node (ref "D7") (pin "C") (pinfunction "C_C") (pintype "passive"))
      (node (ref "Q3") (pin "B") (pinfunction "B_B") (pintype "passive"))
      (node (ref "R73") (pin "2") (pinfunction "2_2") (pintype "passive"))
      (node (ref "R77") (pin "2") (pinfunction "2_2") (pintype "passive"))
    )
    (net (code "45") (name "Net-(D8-PadC)") (class "Default")
      (node (ref "D8") (pin "C") (pinfunction "C_C") (pintype "passive"))
      (node (ref "Q4") (pin "B") (pinfunction "B_B") (pintype "passive"))
      (node (ref "R72") (pin "2") (pinfunction "2_2") (pintype "passive"))
      (node (ref "R76") (pin "2") (pinfunction "2_2") (pintype "passive"))
    )
    (net (code "46") (name "Net-(IC1-IREF)") (class "Default")
      (node (ref "IC1") (pin "23") (pinfunction "IREF_23") (pintype "bidirectional"))
      (node (ref "R6") (pin "1") (pinfunction "1_1") (pintype "passive"))
    )
    (net (code "47") (name "Net-(IC1-OUT2)") (class "Default")
      (node (ref "IC1") (pin "7") (pinfunction "OUT2_7") (pintype "bidirectional"))
      (node (ref "LED9") (pin "RED_C") (pinfunction "RED_RED_C") (pintype "bidirectional"))
    )
    (net (code "48") (name "Net-(IC1-OUT3)") (class "Default")
      (node (ref "IC1") (pin "8") (pinfunction "OUT3_8") (pintype "bidirectional"))
      (node (ref "LED9") (pin "GREEN_C") (pinfunction "GRN_GREEN_C") (pintype "bidirectional"))
    )
    (net (code "49") (name "Net-(IC1-OUT4)") (class "Default")
      (node (ref "IC1") (pin "9") (pinfunction "OUT4_9") (pintype "bidirectional"))
      (node (ref "LED7") (pin "GREEN_C") (pinfunction "GRN_GREEN_C") (pintype "bidirectional"))
    )
    (net (code "50") (name "Net-(IC1-OUT5)") (class "Default")
      (node (ref "IC1") (pin "10") (pinfunction "OUT5_10") (pintype "bidirectional"))
      (node (ref "LED7") (pin "RED_C") (pinfunction "RED_RED_C") (pintype "bidirectional"))
    )
    (net (code "51") (name "Net-(IC1-OUT6)") (class "Default")
      (node (ref "IC1") (pin "11") (pinfunction "OUT6_11") (pintype "bidirectional"))
      (node (ref "LED8") (pin "GREEN_C") (pinfunction "GRN_GREEN_C") (pintype "bidirectional"))
    )
    (net (code "52") (name "Net-(IC1-OUT7)") (class "Default")
      (node (ref "IC1") (pin "12") (pinfunction "OUT7_12") (pintype "bidirectional"))
      (node (ref "LED8") (pin "RED_C") (pinfunction "RED_RED_C") (pintype "bidirectional"))
    )
    (net (code "53") (name "Net-(IC1-OUT8)") (class "Default")
      (node (ref "IC1") (pin "13") (pinfunction "OUT8_13") (pintype "bidirectional"))
      (node (ref "LED10") (pin "GREEN_C") (pinfunction "GRN_GREEN_C") (pintype "bidirectional"))
    )
    (net (code "54") (name "Net-(IC1-OUT9)") (class "Default")
      (node (ref "IC1") (pin "14") (pinfunction "OUT9_14") (pintype "bidirectional"))
      (node (ref "LED10") (pin "RED_C") (pinfunction "RED_RED_C") (pintype "bidirectional"))
    )
    (net (code "55") (name "Net-(IC1-OUT10)") (class "Default")
      (node (ref "IC1") (pin "15") (pinfunction "OUT10_15") (pintype "bidirectional"))
      (node (ref "LED11") (pin "RED_C") (pinfunction "RED_RED_C") (pintype "bidirectional"))
    )
    (net (code "56") (name "Net-(IC1-OUT11)") (class "Default")
      (node (ref "IC1") (pin "16") (pinfunction "OUT11_16") (pintype "bidirectional"))
      (node (ref "LED11") (pin "GREEN_C") (pinfunction "GRN_GREEN_C") (pintype "bidirectional"))
    )
    (net (code "57") (name "Net-(IC1-OUT12)") (class "Default")
      (node (ref "IC1") (pin "17") (pinfunction "OUT12_17") (pintype "bidirectional"))
      (node (ref "LED12") (pin "RED_C") (pinfunction "RED_RED_C") (pintype "bidirectional"))
    )
    (net (code "58") (name "Net-(IC1-OUT13)") (class "Default")
      (node (ref "IC1") (pin "18") (pinfunction "OUT13_18") (pintype "bidirectional"))
      (node (ref "LED12") (pin "GREEN_C") (pinfunction "GRN_GREEN_C") (pintype "bidirectional"))
    )
    (net (code "59") (name "Net-(IC1-VCC)") (class "Default")
      (node (ref "C6") (pin "1") (pinfunction "1_1") (pintype "passive"))
      (node (ref "C8") (pin "1") (pinfunction "1_1") (pintype "passive"))
      (node (ref "IC1") (pin "24") (pinfunction "VCC_24") (pintype "bidirectional"))
      (node (ref "L2") (pin "1") (pinfunction "1_1") (pintype "passive"))
    )
    (net (code "60") (name "Net-(IC2-VI)") (class "Default")
      (node (ref "C19") (pin "1") (pinfunction "1_1") (pintype "passive"))
      (node (ref "IC2") (pin "1") (pinfunction "VI_1") (pintype "input"))
      (node (ref "L3") (pin "2") (pinfunction "2_2") (pintype "passive"))
    )
    (net (code "61") (name "Net-(IC3A-X1)") (class "Default")
      (node (ref "IC3") (pin "14") (pinfunction "X1_14") (pintype "bidirectional"))
      (node (ref "R87") (pin "P$2") (pinfunction "S_P$2") (pintype "passive"))
    )
    (net (code "62") (name "Net-(IC3A-X2)") (class "Default")
      (node (ref "IC3") (pin "15") (pinfunction "X2_15") (pintype "bidirectional"))
      (node (ref "R88") (pin "P$2") (pinfunction "S_P$2") (pintype "passive"))
    )
    (net (code "63") (name "Net-(IC3A-X4)") (class "Default")
      (node (ref "IC3") (pin "1") (pinfunction "X4_1") (pintype "bidirectional"))
      (node (ref "R86") (pin "P$2") (pinfunction "S_P$2") (pintype "passive"))
    )
    (net (code "64") (name "Net-(IC3A-X5)") (class "Default")
      (node (ref "IC3") (pin "5") (pinfunction "X5_5") (pintype "bidirectional"))
      (node (ref "R84") (pin "P$2") (pinfunction "S_P$2") (pintype "passive"))
    )
    (net (code "65") (name "Net-(IC3A-X6)") (class "Default")
      (node (ref "IC3") (pin "2") (pinfunction "X6_2") (pintype "bidirectional"))
      (node (ref "R85") (pin "P$2") (pinfunction "S_P$2") (pintype "passive"))
    )
    (net (code "66") (name "Net-(IC3A-X7)") (class "Default")
      (node (ref "IC3") (pin "4") (pinfunction "X7_4") (pintype "bidirectional"))
      (node (ref "R89") (pin "P$2") (pinfunction "S_P$2") (pintype "passive"))
    )
    (net (code "67") (name "Net-(IC5-PF0{slash}OSC_IN{slash}I2C2_SDA)") (class "Default")
      (node (ref "IC5") (pin "5") (pinfunction "PF0/OSC_IN/I2C2_SDA_5") (pintype "bidirectional"))
      (node (ref "R9") (pin "1") (pinfunction "1_1") (pintype "passive"))
    )
    (net (code "68") (name "Net-(IC5-PF1{slash}OSC_OUT{slash}I2C2_SCL)") (class "Default")
      (node (ref "IC5") (pin "6") (pinfunction "PF1/OSC_OUT/I2C2_SCL_6") (pintype "bidirectional"))
      (node (ref "R8") (pin "1") (pinfunction "1_1") (pintype "passive"))
    )
    (net (code "69") (name "Net-(IC6A-X0)") (class "Default")
      (node (ref "IC6") (pin "13") (pinfunction "X0_13") (pintype "bidirectional"))
      (node (ref "R81") (pin "2") (pinfunction "S_2") (pintype "passive"))
    )
    (net (code "70") (name "Net-(IC6A-X1)") (class "Default")
      (node (ref "IC6") (pin "14") (pinfunction "X1_14") (pintype "bidirectional"))
      (node (ref "R80") (pin "2") (pinfunction "S_2") (pintype "passive"))
    )
    (net (code "71") (name "Net-(IC6A-X2)") (class "Default")
      (node (ref "IC6") (pin "15") (pinfunction "X2_15") (pintype "bidirectional"))
      (node (ref "R79") (pin "2") (pinfunction "S_2") (pintype "passive"))
    )
    (net (code "72") (name "Net-(IC6A-X3)") (class "Default")
      (node (ref "IC6") (pin "12") (pinfunction "X3_12") (pintype "bidirectional"))
      (node (ref "R82") (pin "2") (pinfunction "S_2") (pintype "passive"))
    )
    (net (code "73") (name "Net-(IC6A-X4)") (class "Default")
      (node (ref "IC6") (pin "1") (pinfunction "X4_1") (pintype "bidirectional"))
      (node (ref "R78") (pin "2") (pinfunction "S_2") (pintype "passive"))
    )
    (net (code "74") (name "Net-(IC6A-X6)") (class "Default")
      (node (ref "IC6") (pin "2") (pinfunction "X6_2") (pintype "bidirectional"))
      (node (ref "R83") (pin "2") (pinfunction "S_2") (pintype "passive"))
    )
    (net (code "75") (name "Net-(IC7-VI)") (class "Default")
      (node (ref "C23") (pin "1") (pinfunction "1_1") (pintype "passive"))
      (node (ref "IC7") (pin "3") (pinfunction "VI_3") (pintype "input"))
      (node (ref "L4") (pin "1") (pinfunction "1_1") (pintype "passive"))
    )
    (net (code "76") (name "Net-(IC8A--IN)") (class "Default")
      (node (ref "C28") (pin "1") (pinfunction "1_1") (pintype "passive"))
      (node (ref "IC8") (pin "2") (pinfunction "-IN_2") (pintype "input"))
      (node (ref "R20") (pin "2") (pinfunction "2_2") (pintype "passive"))
      (node (ref "R23") (pin "1") (pinfunction "1_1") (pintype "passive"))
      (node (ref "R32") (pin "1") (pinfunction "1_1") (pintype "passive"))
    )
    (net (code "77") (name "Net-(IC8B--IN)") (class "Default")
      (node (ref "C27") (pin "1") (pinfunction "1_1") (pintype "passive"))
      (node (ref "IC8") (pin "6") (pinfunction "-IN_6") (pintype "input"))
      (node (ref "R19") (pin "2") (pinfunction "2_2") (pintype "passive"))
      (node (ref "R24") (pin "1") (pinfunction "1_1") (pintype "passive"))
      (node (ref "R31") (pin "1") (pinfunction "1_1") (pintype "passive"))
    )
    (net (code "78") (name "Net-(IC9A--IN)") (class "Default")
      (node (ref "C29") (pin "1") (pinfunction "1_1") (pintype "passive"))
      (node (ref "IC9") (pin "2") (pinfunction "-IN_2") (pintype "input"))
      (node (ref "R15") (pin "2") (pinfunction "2_2") (pintype "passive"))
      (node (ref "R22") (pin "1") (pinfunction "1_1") (pintype "passive"))
      (node (ref "R25") (pin "1") (pinfunction "1_1") (pintype "passive"))
    )
    (net (code "79") (name "Net-(IC9B--IN)") (class "Default")
      (node (ref "C31") (pin "1") (pinfunction "1_1") (pintype "passive"))
      (node (ref "IC9") (pin "6") (pinfunction "-IN_6") (pintype "input"))
      (node (ref "R13") (pin "2") (pinfunction "2_2") (pintype "passive"))
      (node (ref "R26") (pin "1") (pinfunction "1_1") (pintype "passive"))
      (node (ref "R27") (pin "1") (pinfunction "1_1") (pintype "passive"))
    )
    (net (code "80") (name "Net-(IC10A--IN)") (class "Default")
      (node (ref "C32") (pin "1") (pinfunction "1_1") (pintype "passive"))
      (node (ref "IC10") (pin "2") (pinfunction "-IN_2") (pintype "input"))
      (node (ref "R14") (pin "2") (pinfunction "2_2") (pintype "passive"))
      (node (ref "R21") (pin "1") (pinfunction "1_1") (pintype "passive"))
      (node (ref "R28") (pin "1") (pinfunction "1_1") (pintype "passive"))
    )
    (net (code "81") (name "Net-(IC10B--IN)") (class "Default")
      (node (ref "C35") (pin "1") (pinfunction "1_1") (pintype "passive"))
      (node (ref "IC10") (pin "6") (pinfunction "-IN_6") (pintype "input"))
      (node (ref "R16") (pin "2") (pinfunction "2_2") (pintype "passive"))
      (node (ref "R29") (pin "1") (pinfunction "1_1") (pintype "passive"))
      (node (ref "R30") (pin "1") (pinfunction "1_1") (pintype "passive"))
    )
    (net (code "82") (name "Net-(IC12A--IN)") (class "Default")
      (node (ref "C44") (pin "1") (pinfunction "1_1") (pintype "passive"))
      (node (ref "IC12") (pin "2") (pinfunction "-IN_2") (pintype "input"))
      (node (ref "R41") (pin "2") (pinfunction "2_2") (pintype "passive"))
      (node (ref "R47") (pin "1") (pinfunction "1_1") (pintype "passive"))
    )
    (net (code "83") (name "Net-(IC12A-OUT)") (class "Default")
      (node (ref "C44") (pin "2") (pinfunction "2_2") (pintype "passive"))
      (node (ref "IC12") (pin "1") (pinfunction "OUT_1") (pintype "output"))
      (node (ref "IC12") (pin "5") (pinfunction "+IN_5") (pintype "input"))
      (node (ref "R35") (pin "2") (pinfunction "2_2") (pintype "passive"))
    )
    (net (code "84") (name "Net-(IC12B--IN)") (class "Default")
      (node (ref "IC12") (pin "6") (pinfunction "-IN_6") (pintype "input"))
      (node (ref "LED4") (pin "2") (pinfunction "2_2") (pintype "bidirectional"))
      (node (ref "R54") (pin "1") (pinfunction "1_1") (pintype "passive"))
    )
    (net (code "85") (name "Net-(IC12B-OUT)") (class "Default")
      (node (ref "IC12") (pin "7") (pinfunction "OUT_7") (pintype "output"))
      (node (ref "LED4") (pin "1") (pinfunction "1_1") (pintype "bidirectional"))
    )
    (net (code "86") (name "Net-(IC12C-+IN)") (class "Default")
      (node (ref "C45") (pin "2") (pinfunction "2_2") (pintype "passive"))
      (node (ref "IC12") (pin "10") (pinfunction "+IN_10") (pintype "input"))
      (node (ref "IC12") (pin "14") (pinfunction "OUT_14") (pintype "output"))
      (node (ref "R34") (pin "2") (pinfunction "2_2") (pintype "passive"))
    )
    (net (code "87") (name "Net-(IC12C--IN)") (class "Default")
      (node (ref "IC12") (pin "9") (pinfunction "-IN_9") (pintype "input"))
      (node (ref "LED6") (pin "2") (pinfunction "2_2") (pintype "bidirectional"))
      (node (ref "R55") (pin "1") (pinfunction "1_1") (pintype "passive"))
    )
    (net (code "88") (name "Net-(IC12C-OUT)") (class "Default")
      (node (ref "IC12") (pin "8") (pinfunction "OUT_8") (pintype "output"))
      (node (ref "LED6") (pin "1") (pinfunction "1_1") (pintype "bidirectional"))
    )
    (net (code "89") (name "Net-(IC12D--IN)") (class "Default")
      (node (ref "C45") (pin "1") (pinfunction "1_1") (pintype "passive"))
      (node (ref "IC12") (pin "13") (pinfunction "-IN_13") (pintype "input"))
      (node (ref "R42") (pin "2") (pinfunction "2_2") (pintype "passive"))
      (node (ref "R50") (pin "1") (pinfunction "1_1") (pintype "passive"))
    )
    (net (code "90") (name "Net-(IC13A--IN)") (class "Default")
      (node (ref "C46") (pin "1") (pinfunction "1_1") (pintype "passive"))
      (node (ref "IC13") (pin "2") (pinfunction "-IN_2") (pintype "input"))
      (node (ref "R43") (pin "2") (pinfunction "2_2") (pintype "passive"))
      (node (ref "R49") (pin "1") (pinfunction "1_1") (pintype "passive"))
    )
    (net (code "91") (name "Net-(IC13A-OUT)") (class "Default")
      (node (ref "C46") (pin "2") (pinfunction "2_2") (pintype "passive"))
      (node (ref "IC13") (pin "1") (pinfunction "OUT_1") (pintype "output"))
      (node (ref "IC13") (pin "5") (pinfunction "+IN_5") (pintype "input"))
      (node (ref "R36") (pin "2") (pinfunction "2_2") (pintype "passive"))
    )
    (net (code "92") (name "Net-(IC13B--IN)") (class "Default")
      (node (ref "IC13") (pin "6") (pinfunction "-IN_6") (pintype "input"))
      (node (ref "LED3") (pin "2") (pinfunction "2_2") (pintype "bidirectional"))
      (node (ref "R56") (pin "1") (pinfunction "1_1") (pintype "passive"))
    )
    (net (code "93") (name "Net-(IC13B-OUT)") (class "Default")
      (node (ref "IC13") (pin "7") (pinfunction "OUT_7") (pintype "output"))
      (node (ref "LED3") (pin "1") (pinfunction "1_1") (pintype "bidirectional"))
    )
    (net (code "94") (name "Net-(IC13C-+IN)") (class "Default")
      (node (ref "C47") (pin "2") (pinfunction "2_2") (pintype "passive"))
      (node (ref "IC13") (pin "10") (pinfunction "+IN_10") (pintype "input"))
      (node (ref "IC13") (pin "14") (pinfunction "OUT_14") (pintype "output"))
      (node (ref "R38") (pin "2") (pinfunction "2_2") (pintype "passive"))
    )
    (net (code "95") (name "Net-(IC13C--IN)") (class "Default")
      (node (ref "IC13") (pin "9") (pinfunction "-IN_9") (pintype "input"))
      (node (ref "LED2") (pin "2") (pinfunction "2_2") (pintype "bidirectional"))
      (node (ref "R57") (pin "1") (pinfunction "1_1") (pintype "passive"))
    )
    (net (code "96") (name "Net-(IC13C-OUT)") (class "Default")
      (node (ref "IC13") (pin "8") (pinfunction "OUT_8") (pintype "output"))
      (node (ref "LED2") (pin "1") (pinfunction "1_1") (pintype "bidirectional"))
    )
    (net (code "97") (name "Net-(IC13D--IN)") (class "Default")
      (node (ref "C47") (pin "1") (pinfunction "1_1") (pintype "passive"))
      (node (ref "IC13") (pin "13") (pinfunction "-IN_13") (pintype "input"))
      (node (ref "R44") (pin "2") (pinfunction "2_2") (pintype "passive"))
      (node (ref "R53") (pin "1") (pinfunction "1_1") (pintype "passive"))
    )
    (net (code "98") (name "Net-(IC14A--IN)") (class "Default")
      (node (ref "C48") (pin "1") (pinfunction "1_1") (pintype "passive"))
      (node (ref "IC14") (pin "2") (pinfunction "-IN_2") (pintype "input"))
      (node (ref "R45") (pin "2") (pinfunction "2_2") (pintype "passive"))
      (node (ref "R51") (pin "1") (pinfunction "1_1") (pintype "passive"))
    )
    (net (code "99") (name "Net-(IC14A-OUT)") (class "Default")
      (node (ref "C48") (pin "2") (pinfunction "2_2") (pintype "passive"))
      (node (ref "IC14") (pin "1") (pinfunction "OUT_1") (pintype "output"))
      (node (ref "IC14") (pin "5") (pinfunction "+IN_5") (pintype "input"))
      (node (ref "R37") (pin "2") (pinfunction "2_2") (pintype "passive"))
    )
    (net (code "100") (name "Net-(IC14B--IN)") (class "Default")
      (node (ref "IC14") (pin "6") (pinfunction "-IN_6") (pintype "input"))
      (node (ref "LED5") (pin "2") (pinfunction "2_2") (pintype "bidirectional"))
      (node (ref "R58") (pin "1") (pinfunction "1_1") (pintype "passive"))
    )
    (net (code "101") (name "Net-(IC14B-OUT)") (class "Default")
      (node (ref "IC14") (pin "7") (pinfunction "OUT_7") (pintype "output"))
      (node (ref "LED5") (pin "1") (pinfunction "1_1") (pintype "bidirectional"))
    )
    (net (code "102") (name "Net-(IC14C-+IN)") (class "Default")
      (node (ref "C49") (pin "2") (pinfunction "2_2") (pintype "passive"))
      (node (ref "IC14") (pin "10") (pinfunction "+IN_10") (pintype "input"))
      (node (ref "IC14") (pin "14") (pinfunction "OUT_14") (pintype "output"))
      (node (ref "R39") (pin "2") (pinfunction "2_2") (pintype "passive"))
    )
    (net (code "103") (name "Net-(IC14C--IN)") (class "Default")
      (node (ref "IC14") (pin "9") (pinfunction "-IN_9") (pintype "input"))
      (node (ref "LED1") (pin "2") (pinfunction "2_2") (pintype "bidirectional"))
      (node (ref "R59") (pin "1") (pinfunction "1_1") (pintype "passive"))
    )
    (net (code "104") (name "Net-(IC14C-OUT)") (class "Default")
      (node (ref "IC14") (pin "8") (pinfunction "OUT_8") (pintype "output"))
      (node (ref "LED1") (pin "1") (pinfunction "1_1") (pintype "bidirectional"))
    )
    (net (code "105") (name "Net-(IC14D--IN)") (class "Default")
      (node (ref "C49") (pin "1") (pinfunction "1_1") (pintype "passive"))
      (node (ref "IC14") (pin "13") (pinfunction "-IN_13") (pintype "input"))
      (node (ref "R46") (pin "2") (pinfunction "2_2") (pintype "passive"))
      (node (ref "R52") (pin "1") (pinfunction "1_1") (pintype "passive"))
    )
    (net (code "106") (name "Net-(J1-3)") (class "Default")
      (node (ref "J1") (pin "P3") (pinfunction "3_P3") (pintype "passive"))
      (node (ref "R39") (pin "1") (pinfunction "1_1") (pintype "passive"))
      (node (ref "R46") (pin "1") (pinfunction "1_1") (pintype "passive"))
    )
    (net (code "107") (name "Net-(J2-3)") (class "Default")
      (node (ref "J2") (pin "P3") (pinfunction "3_P3") (pintype "passive"))
      (node (ref "R37") (pin "1") (pinfunction "1_1") (pintype "passive"))
      (node (ref "R45") (pin "1") (pinfunction "1_1") (pintype "passive"))
    )
    (net (code "108") (name "Net-(J3-3)") (class "Default")
      (node (ref "J3") (pin "P3") (pinfunction "3_P3") (pintype "passive"))
      (node (ref "R38") (pin "1") (pinfunction "1_1") (pintype "passive"))
      (node (ref "R44") (pin "1") (pinfunction "1_1") (pintype "passive"))
    )
    (net (code "109") (name "Net-(J4-3)") (class "Default")
      (node (ref "J4") (pin "P3") (pinfunction "3_P3") (pintype "passive"))
      (node (ref "R36") (pin "1") (pinfunction "1_1") (pintype "passive"))
      (node (ref "R43") (pin "1") (pinfunction "1_1") (pintype "passive"))
    )
    (net (code "110") (name "Net-(J5-3)") (class "Default")
      (node (ref "J5") (pin "P3") (pinfunction "3_P3") (pintype "passive"))
      (node (ref "R34") (pin "1") (pinfunction "1_1") (pintype "passive"))
      (node (ref "R42") (pin "1") (pinfunction "1_1") (pintype "passive"))
    )
    (net (code "111") (name "Net-(J6-3)") (class "Default")
      (node (ref "J6") (pin "P3") (pinfunction "3_P3") (pintype "passive"))
      (node (ref "R35") (pin "1") (pinfunction "1_1") (pintype "passive"))
      (node (ref "R41") (pin "1") (pinfunction "1_1") (pintype "passive"))
    )
    (net (code "112") (name "Net-(J7-2)") (class "Default")
      (node (ref "J7") (pin "P2") (pinfunction "2_P2") (pintype "passive"))
      (node (ref "R65") (pin "2") (pinfunction "2_2") (pintype "passive"))
    )
    (net (code "113") (name "Net-(J7-3)") (class "Default")
      (node (ref "J7") (pin "P3") (pinfunction "3_P3") (pintype "passive"))
      (node (ref "R66") (pin "1") (pinfunction "1_1") (pintype "passive"))
    )
    (net (code "114") (name "Net-(J8-2)") (class "Default")
      (node (ref "J8") (pin "P2") (pinfunction "2_P2") (pintype "passive"))
      (node (ref "R62") (pin "2") (pinfunction "2_2") (pintype "passive"))
    )
    (net (code "115") (name "Net-(J8-3)") (class "Default")
      (node (ref "J8") (pin "P3") (pinfunction "3_P3") (pintype "passive"))
      (node (ref "R77") (pin "1") (pinfunction "1_1") (pintype "passive"))
    )
    (net (code "116") (name "Net-(J9-2)") (class "Default")
      (node (ref "J9") (pin "P2") (pinfunction "2_P2") (pintype "passive"))
      (node (ref "R63") (pin "2") (pinfunction "2_2") (pintype "passive"))
    )
    (net (code "117") (name "Net-(J9-3)") (class "Default")
      (node (ref "J9") (pin "P3") (pinfunction "3_P3") (pintype "passive"))
      (node (ref "R68") (pin "1") (pinfunction "1_1") (pintype "passive"))
    )
    (net (code "118") (name "Net-(J10-2)") (class "Default")
      (node (ref "J10") (pin "P2") (pinfunction "2_P2") (pintype "passive"))
      (node (ref "R61") (pin "2") (pinfunction "2_2") (pintype "passive"))
    )
    (net (code "119") (name "Net-(J10-3)") (class "Default")
      (node (ref "J10") (pin "P3") (pinfunction "3_P3") (pintype "passive"))
      (node (ref "R76") (pin "1") (pinfunction "1_1") (pintype "passive"))
    )
    (net (code "120") (name "Net-(J11-2)") (class "Default")
      (node (ref "J11") (pin "P2") (pinfunction "2_P2") (pintype "passive"))
      (node (ref "R64") (pin "2") (pinfunction "2_2") (pintype "passive"))
    )
    (net (code "121") (name "Net-(J11-3)") (class "Default")
      (node (ref "J11") (pin "P3") (pinfunction "3_P3") (pintype "passive"))
      (node (ref "R67") (pin "1") (pinfunction "1_1") (pintype "passive"))
    )
    (net (code "122") (name "Net-(J12-2)") (class "Default")
      (node (ref "J12") (pin "P2") (pinfunction "2_P2") (pintype "passive"))
      (node (ref "R60") (pin "2") (pinfunction "2_2") (pintype "passive"))
    )
    (net (code "123") (name "Net-(J12-3)") (class "Default")
      (node (ref "J12") (pin "P3") (pinfunction "3_P3") (pintype "passive"))
      (node (ref "R75") (pin "1") (pinfunction "1_1") (pintype "passive"))
    )
    (net (code "124") (name "Net-(J13-3)") (class "Default")
      (node (ref "C38") (pin "1") (pinfunction "1_1") (pintype "passive"))
      (node (ref "J13") (pin "P3") (pinfunction "3_P3") (pintype "passive"))
      (node (ref "R30") (pin "2") (pinfunction "2_2") (pintype "passive"))
    )
    (net (code "125") (name "Net-(J14-3)") (class "Default")
      (node (ref "C39") (pin "1") (pinfunction "1_1") (pintype "passive"))
      (node (ref "J14") (pin "P3") (pinfunction "3_P3") (pintype "passive"))
      (node (ref "R28") (pin "2") (pinfunction "2_2") (pintype "passive"))
    )
    (net (code "126") (name "Net-(J15-3)") (class "Default")
      (node (ref "C37") (pin "1") (pinfunction "1_1") (pintype "passive"))
      (node (ref "J15") (pin "P3") (pinfunction "3_P3") (pintype "passive"))
      (node (ref "R27") (pin "2") (pinfunction "2_2") (pintype "passive"))
    )
    (net (code "127") (name "Net-(J16-3)") (class "Default")
      (node (ref "C40") (pin "1") (pinfunction "1_1") (pintype "passive"))
      (node (ref "J16") (pin "P3") (pinfunction "3_P3") (pintype "passive"))
      (node (ref "R25") (pin "2") (pinfunction "2_2") (pintype "passive"))
    )
    (net (code "128") (name "Net-(J17-3)") (class "Default")
      (node (ref "C36") (pin "1") (pinfunction "1_1") (pintype "passive"))
      (node (ref "J17") (pin "P3") (pinfunction "3_P3") (pintype "passive"))
      (node (ref "R31") (pin "2") (pinfunction "2_2") (pintype "passive"))
    )
    (net (code "129") (name "Net-(J18-3)") (class "Default")
      (node (ref "C42") (pin "1") (pinfunction "1_1") (pintype "passive"))
      (node (ref "J18") (pin "P3") (pinfunction "3_P3") (pintype "passive"))
      (node (ref "R32") (pin "2") (pinfunction "2_2") (pintype "passive"))
    )
    (net (code "130") (name "Net-(JP3-Pad2)") (class "Default")
      (node (ref "JP3") (pin "2") (pinfunction "2_2") (pintype "passive"))
      (node (ref "R5") (pin "2") (pinfunction "2_2") (pintype "passive"))
    )
    (net (code "131") (name "Net-(JP3-Pad3)") (class "Default")
      (node (ref "JP3") (pin "3") (pinfunction "3_3") (pintype "passive"))
      (node (ref "R7") (pin "2") (pinfunction "2_2") (pintype "passive"))
    )
    (net (code "132") (name "Net-(JP4-Pad2)") (class "Default")
      (node (ref "JP4") (pin "2") (pinfunction "2_2") (pintype "passive"))
      (node (ref "R10") (pin "2") (pinfunction "2_2") (pintype "passive"))
    )
    (net (code "133") (name "Net-(JP4-Pad3)") (class "Default")
      (node (ref "JP4") (pin "3") (pinfunction "3_3") (pintype "passive"))
      (node (ref "R11") (pin "2") (pinfunction "2_2") (pintype "passive"))
    )
    (net (code "134") (name "Net-(Q1B-2)") (class "Default")
      (node (ref "C4") (pin "2") (pinfunction "2_2") (pintype "passive"))
      (node (ref "Q1") (pin "3") (pinfunction "2_3") (pintype "passive"))
      (node (ref "R8") (pin "2") (pinfunction "2_2") (pintype "passive"))
    )
    (net (code "135") (name "Net-(R78A-A)") (class "Default")
      (node (ref "R17") (pin "1") (pinfunction "1_1") (pintype "passive"))
      (node (ref "R78") (pin "B") (pinfunction "A_B") (pintype "passive"))
    )
    (net (code "136") (name "Net-(R79A-A)") (class "Default")
      (node (ref "R3") (pin "1") (pinfunction "1_1") (pintype "passive"))
      (node (ref "R79") (pin "B") (pinfunction "A_B") (pintype "passive"))
    )
    (net (code "137") (name "Net-(R80A-A)") (class "Default")
      (node (ref "R1") (pin "1") (pinfunction "1_1") (pintype "passive"))
      (node (ref "R80") (pin "B") (pinfunction "A_B") (pintype "passive"))
    )
    (net (code "138") (name "Net-(R81A-A)") (class "Default")
      (node (ref "R2") (pin "1") (pinfunction "1_1") (pintype "passive"))
      (node (ref "R81") (pin "B") (pinfunction "A_B") (pintype "passive"))
    )
    (net (code "139") (name "Net-(R82A-A)") (class "Default")
      (node (ref "R4") (pin "1") (pinfunction "1_1") (pintype "passive"))
      (node (ref "R82") (pin "B") (pinfunction "A_B") (pintype "passive"))
    )
    (net (code "140") (name "Net-(R83A-A)") (class "Default")
      (node (ref "R18") (pin "1") (pinfunction "1_1") (pintype "passive"))
      (node (ref "R83") (pin "B") (pinfunction "A_B") (pintype "passive"))
    )
    (net (code "141") (name "POTS_ADDR_A") (class "Default")
      (node (ref "IC3") (pin "9") (pinfunction "C_9") (pintype "input"))
      (node (ref "IC5") (pin "21") (pinfunction "PA5/SPI1_SCK/I2S1_CK/TIM2_CH1/ADC_IN5/DAC1_OUT2_21") (pintype "bidirectional"))
      (node (ref "IC6") (pin "11") (pinfunction "A_11") (pintype "input"))
    )
    (net (code "142") (name "POTS_ADDR_B") (class "Default")
      (node (ref "IC3") (pin "10") (pinfunction "B_10") (pintype "input"))
      (node (ref "IC5") (pin "20") (pinfunction "PA4/SPI1_NSS/I2S1_WS/SPI3_NSS/I2S3_WS/USART2_CK/TIM3_CH2/ADC_IN4/DAC1_OUT1_20") (pintype "bidirectional"))
      (node (ref "IC6") (pin "10") (pinfunction "B_10") (pintype "input"))
    )
    (net (code "143") (name "POTS_ADDR_C") (class "Default")
      (node (ref "IC3") (pin "11") (pinfunction "A_11") (pintype "input"))
      (node (ref "IC5") (pin "18") (pinfunction "PA3/SPI3_MOSI/I2S3_SD/USART2_RX/TIM2_CH4/TIM5_CH4/ADC_IN3_18") (pintype "bidirectional"))
      (node (ref "IC6") (pin "9") (pinfunction "C_9") (pintype "input"))
    )
    (net (code "144") (name "RESET") (class "Default")
      (node (ref "IC5") (pin "7") (pinfunction "NRST_7") (pintype "bidirectional"))
      (node (ref "JP6") (pin "4") (pinfunction "4_4") (pintype "passive"))
      (node (ref "R12") (pin "1") (pinfunction "1_1") (pintype "passive"))
    )
    (net (code "145") (name "RIGHT_RX") (class "Default")
      (node (ref "IC5") (pin "25") (pinfunction "PC5/USART1_RX/ADC_IN15_25") (pintype "bidirectional"))
      (node (ref "R10") (pin "1") (pinfunction "1_1") (pintype "passive"))
    )
    (net (code "146") (name "RIGHT_TX") (class "Default")
      (node (ref "IC5") (pin "24") (pinfunction "PC4/USART1_TX/ADC_IN14_24") (pintype "bidirectional"))
      (node (ref "R11") (pin "1") (pinfunction "1_1") (pintype "passive"))
    )
    (net (code "147") (name "STAGE_LED_1") (class "Default")
      (node (ref "IC5") (pin "45") (pinfunction "PA12/SPI1_SCK/I2S1_CK/USART1_RTS/CAN_TX/TIM4_CH2/TIM5_CH3_45") (pintype "bidirectional"))
      (node (ref "R17") (pin "2") (pinfunction "2_2") (pintype "passive"))
    )
    (net (code "148") (name "STAGE_LED_2") (class "Default")
      (node (ref "IC5") (pin "2") (pinfunction "PC13/TIMESTAMP/RTC_TAMPER1_2") (pintype "bidirectional"))
      (node (ref "R3") (pin "2") (pinfunction "2_2") (pintype "passive"))
    )
    (net (code "149") (name "STAGE_LED_3") (class "Default")
      (node (ref "IC5") (pin "3") (pinfunction "PC14/OSC32_IN_3") (pintype "bidirectional"))
      (node (ref "R1") (pin "2") (pinfunction "2_2") (pintype "passive"))
    )
    (net (code "150") (name "STAGE_LED_4") (class "Default")
      (node (ref "IC5") (pin "4") (pinfunction "PC15/OSC32_OUT_4") (pintype "bidirectional"))
      (node (ref "R2") (pin "2") (pinfunction "2_2") (pintype "passive"))
    )
    (net (code "151") (name "STAGE_LED_5") (class "Default")
      (node (ref "IC5") (pin "16") (pinfunction "PA2/SPI3_MISO/I2S3_MCK/USART2_TX/TIM2_CH3/TIM5_CH3/ADC_IN2_16") (pintype "bidirectional"))
      (node (ref "R4") (pin "2") (pinfunction "2_2") (pintype "passive"))
    )
    (net (code "152") (name "STAGE_LED_6") (class "Default")
      (node (ref "IC5") (pin "28") (pinfunction "PB2/SDADC_AIN4P/SDADC2_AIN6P_28") (pintype "bidirectional"))
      (node (ref "R18") (pin "2") (pinfunction "2_2") (pintype "passive"))
    )
    (net (code "153") (name "SWCLK") (class "Default")
      (node (ref "IC5") (pin "49") (pinfunction "PA14/I2C1_SDA/JTCK-SWCLK_49") (pintype "bidirectional"))
      (node (ref "JP6") (pin "3") (pinfunction "3_3") (pintype "passive"))
    )
    (net (code "154") (name "SWDIO") (class "Default")
      (node (ref "IC5") (pin "46") (pinfunction "PA13/SPI1_MISO/I2S1_MCK/USART3_CTS/TIM4_CH3/TIM5_CH4/JTMS-SWDIO_46") (pintype "bidirectional"))
      (node (ref "JP6") (pin "2") (pinfunction "2_2") (pintype "passive"))
    )
    (net (code "155") (name "SW_MODE_1") (class "Default")
      (node (ref "IC5") (pin "8") (pinfunction "PC0/TIM5_CH1/ADC_IN10_8") (pintype "bidirectional"))
      (node (ref "SW1") (pin "3") (pinfunction "3_3") (pintype "passive"))
      (node (ref "SW1") (pin "4") (pinfunction "4_4") (pintype "passive"))
    )
    (net (code "156") (name "SW_MODE_2") (class "Default")
      (node (ref "IC5") (pin "9") (pinfunction "PC1/TIM5_CH2/ADC_IN11_9") (pintype "bidirectional"))
      (node (ref "SW2") (pin "3") (pinfunction "3_3") (pintype "passive"))
      (node (ref "SW2") (pin "4") (pinfunction "4_4") (pintype "passive"))
    )
    (net (code "157") (name "SW_MODE_3") (class "Default")
      (node (ref "IC5") (pin "10") (pinfunction "PC2/SPI2_MISO/I2S2_MCK/TIM5_CH3/ADC_IN12_10") (pintype "bidirectional"))
      (node (ref "SW3") (pin "3") (pinfunction "3_3") (pintype "passive"))
      (node (ref "SW3") (pin "4") (pinfunction "4_4") (pintype "passive"))
    )
    (net (code "158") (name "SW_MODE_4") (class "Default")
      (node (ref "IC5") (pin "11") (pinfunction "PC3/SPI2_MOSI/I2S2_SD/TIM5_CH4/ADC_IN13_11") (pintype "bidirectional"))
      (node (ref "SW4") (pin "3") (pinfunction "3_3") (pintype "passive"))
      (node (ref "SW4") (pin "4") (pinfunction "4_4") (pintype "passive"))
    )
    (net (code "159") (name "SW_MODE_5") (class "Default")
      (node (ref "IC5") (pin "14") (pinfunction "PA0/USART2_CTS/TIM2_CH1/TIM5_CH1/ADC_IN0_14") (pintype "bidirectional"))
      (node (ref "SW5") (pin "3") (pinfunction "3_3") (pintype "passive"))
      (node (ref "SW5") (pin "4") (pinfunction "4_4") (pintype "passive"))
    )
    (net (code "160") (name "SW_MODE_6") (class "Default")
      (node (ref "IC5") (pin "15") (pinfunction "PA1/SPI3_SCK/I2S3_CK/USART2_RTS/TIM2_CH2/TIM5_CH2/ADC_IN1_15") (pintype "bidirectional"))
      (node (ref "SW6") (pin "3") (pinfunction "3_3") (pintype "passive"))
      (node (ref "SW6") (pin "4") (pinfunction "4_4") (pintype "passive"))
    )
    (net (code "161") (name "VCC") (class "Default")
      (node (ref "C21") (pin "1") (pinfunction "1_1") (pintype "passive"))
      (node (ref "C25") (pin "1") (pinfunction "1_1") (pintype "passive"))
      (node (ref "C50") (pin "1") (pinfunction "1_1") (pintype "passive"))
      (node (ref "C52") (pin "1") (pinfunction "1_1") (pintype "passive"))
      (node (ref "C54") (pin "1") (pinfunction "1_1") (pintype "passive"))
      (node (ref "IC12") (pin "4") (pinfunction "V+_4") (pintype "power_in"))
      (node (ref "IC13") (pin "4") (pinfunction "V+_4") (pintype "power_in"))
      (node (ref "IC14") (pin "4") (pinfunction "V+_4") (pintype "power_in"))
      (node (ref "L5") (pin "1") (pinfunction "1_1") (pintype "passive"))
    )
    (net (code "162") (name "VEE") (class "Default")
      (node (ref "C1") (pin "2") (pinfunction "2_2") (pintype "passive"))
      (node (ref "C2") (pin "2") (pinfunction "2_2") (pintype "passive"))
      (node (ref "C51") (pin "2") (pinfunction "2_2") (pintype "passive"))
      (node (ref "C53") (pin "2") (pinfunction "2_2") (pintype "passive"))
      (node (ref "C55") (pin "2") (pinfunction "2_2") (pintype "passive"))
      (node (ref "IC12") (pin "11") (pinfunction "V-_11") (pintype "power_in"))
      (node (ref "IC13") (pin "11") (pinfunction "V-_11") (pintype "power_in"))
      (node (ref "IC14") (pin "11") (pinfunction "V-_11") (pintype "power_in"))
      (node (ref "L1") (pin "1") (pinfunction "1_1") (pintype "passive"))
      (node (ref "R33") (pin "1") (pinfunction "1_1") (pintype "passive"))
    )
    (net (code "163") (name "VREF_BIAS") (class "Default")
      (node (ref "C43") (pin "1") (pinfunction "1_1") (pintype "passive"))
      (node (ref "IC12") (pin "12") (pinfunction "+IN_12") (pintype "input"))
      (node (ref "IC12") (pin "3") (pinfunction "+IN_3") (pintype "input"))
      (node (ref "IC13") (pin "12") (pinfunction "+IN_12") (pintype "input"))
      (node (ref "IC13") (pin "3") (pinfunction "+IN_3") (pintype "input"))
      (node (ref "IC14") (pin "12") (pinfunction "+IN_12") (pintype "input"))
      (node (ref "IC14") (pin "3") (pinfunction "+IN_3") (pintype "input"))
      (node (ref "R40") (pin "1") (pinfunction "1_1") (pintype "passive"))
      (node (ref "R48") (pin "2") (pinfunction "2_2") (pintype "passive"))
    )
    (net (code "164") (name "unconnected-(IC1-OUT0-Pad5)") (class "Default")
      (node (ref "IC1") (pin "5") (pinfunction "OUT0_5") (pintype "bidirectional"))
    )
    (net (code "165") (name "unconnected-(IC1-OUT1-Pad6)") (class "Default")
      (node (ref "IC1") (pin "6") (pinfunction "OUT1_6") (pintype "bidirectional"))
    )
    (net (code "166") (name "unconnected-(IC1-OUT14-Pad19)") (class "Default")
      (node (ref "IC1") (pin "19") (pinfunction "OUT14_19") (pintype "bidirectional"))
    )
    (net (code "167") (name "unconnected-(IC1-OUT15-Pad20)") (class "Default")
      (node (ref "IC1") (pin "20") (pinfunction "OUT15_20") (pintype "bidirectional"))
    )
    (net (code "168") (name "unconnected-(IC1-SOUT-Pad22)") (class "Default")
      (node (ref "IC1") (pin "22") (pinfunction "SOUT_22") (pintype "bidirectional"))
    )
    (net (code "169") (name "unconnected-(IC2-EN-Pad4)") (class "Default")
      (node (ref "IC2") (pin "4") (pinfunction "EN_4") (pintype "input"))
    )
    (net (code "170") (name "unconnected-(IC3A-X0-Pad13)") (class "Default")
      (node (ref "IC3") (pin "13") (pinfunction "X0_13") (pintype "bidirectional"))
    )
    (net (code "171") (name "unconnected-(IC3A-X3-Pad12)") (class "Default")
      (node (ref "IC3") (pin "12") (pinfunction "X3_12") (pintype "bidirectional"))
    )
    (net (code "172") (name "unconnected-(IC4-VOUTF-Pad9)") (class "Default")
      (node (ref "IC4") (pin "9") (pinfunction "VOUTF_9") (pintype "output"))
    )
    (net (code "173") (name "unconnected-(IC4-VOUTH-Pad8)") (class "Default")
      (node (ref "IC4") (pin "8") (pinfunction "VOUTH_8") (pintype "output"))
    )
    (net (code "174") (name "unconnected-(IC5-PB3{slash}SPI1_SCK{slash}I2S1_CK{slash}SPI3_SCK{slash}I2S3_CK{slash}USART2_TX{slash}TIM2_CH2{slash}JTDO{slash}SPI3_SCK{slash}JTDO-Pad55)") (class "Default")
      (node (ref "IC5") (pin "55") (pinfunction "PB3/SPI1_SCK/I2S1_CK/SPI3_SCK/I2S3_CK/USART2_TX/TIM2_CH2/JTDO/SPI3_SCK/JTDO_55") (pintype "bidirectional"))
    )
    (net (code "175") (name "unconnected-(IC5-PB4{slash}SPI1_MISO{slash}I2S1_MCK{slash}SPI3_MISO{slash}I2S3_MCK{slash}USART2_RX{slash}TIM3_CH1{slash}NJTRST-Pad56)") (class "Default")
      (node (ref "IC5") (pin "56") (pinfunction "PB4/SPI1_MISO/I2S1_MCK/SPI3_MISO/I2S3_MCK/USART2_RX/TIM3_CH1/NJTRST_56") (pintype "bidirectional"))
    )
    (net (code "176") (name "unconnected-(IC5-PC6{slash}SPI1_NSS{slash}I2S1_WS{slash}TIM3_CH1-Pad37)") (class "Default")
      (node (ref "IC5") (pin "37") (pinfunction "PC6/SPI1_NSS/I2S1_WS/TIM3_CH1_37") (pintype "bidirectional"))
    )
    (net (code "177") (name "unconnected-(IC5-PC11{slash}SPI3_MISO{slash}I2S3_MCK{slash}USART3_RX-Pad52)") (class "Default")
      (node (ref "IC5") (pin "52") (pinfunction "PC11/SPI3_MISO/I2S3_MCK/USART3_RX_52") (pintype "bidirectional"))
    )
    (net (code "178") (name "unconnected-(IC5-PD2{slash}TIM3_ETR-Pad54)") (class "Default")
      (node (ref "IC5") (pin "54") (pinfunction "PD2/TIM3_ETR_54") (pintype "bidirectional"))
    )
    (net (code "179") (name "unconnected-(IC5-PD8{slash}SPI2_SCK{slash}I2S2_CK{slash}USART3_TX{slash}SDADC3_AIN6P-Pad36)") (class "Default")
      (node (ref "IC5") (pin "36") (pinfunction "PD8/SPI2_SCK/I2S2_CK/USART3_TX/SDADC3_AIN6P_36") (pintype "bidirectional"))
    )
    (net (code "180") (name "unconnected-(IC5-PF6{slash}SPI1_MOSI{slash}I2S1_SD{slash}USART3_RTS{slash}TIM4_CH4{slash}I2C2_SCL-Pad47)") (class "Default")
      (node (ref "IC5") (pin "47") (pinfunction "PF6/SPI1_MOSI/I2S1_SD/USART3_RTS/TIM4_CH4/I2C2_SCL_47") (pintype "bidirectional"))
    )
    (net (code "181") (name "unconnected-(IC5-PF7{slash}I2C2_SDA{slash}USART2_CK-Pad48)") (class "Default")
      (node (ref "IC5") (pin "48") (pinfunction "PF7/I2C2_SDA/USART2_CK_48") (pintype "bidirectional"))
    )
    (net (code "182") (name "unconnected-(IC6A-X5-Pad5)") (class "Default")
      (node (ref "IC6") (pin "5") (pinfunction "X5_5") (pintype "bidirectional"))
    )
    (net (code "183") (name "unconnected-(IC6A-X7-Pad4)") (class "Default")
      (node (ref "IC6") (pin "4") (pinfunction "X7_4") (pintype "bidirectional"))
    )
    (net (code "184") (name "unconnected-(J1-2-PadP2)") (class "Default")
      (node (ref "J1") (pin "P2") (pinfunction "2_P2") (pintype "passive"))
    )
    (net (code "185") (name "unconnected-(J2-2-PadP2)") (class "Default")
      (node (ref "J2") (pin "P2") (pinfunction "2_P2") (pintype "passive"))
    )
    (net (code "186") (name "unconnected-(J3-2-PadP2)") (class "Default")
      (node (ref "J3") (pin "P2") (pinfunction "2_P2") (pintype "passive"))
    )
    (net (code "187") (name "unconnected-(J4-2-PadP2)") (class "Default")
      (node (ref "J4") (pin "P2") (pinfunction "2_P2") (pintype "passive"))
    )
    (net (code "188") (name "unconnected-(J5-2-PadP2)") (class "Default")
      (node (ref "J5") (pin "P2") (pinfunction "2_P2") (pintype "passive"))
    )
    (net (code "189") (name "unconnected-(J6-2-PadP2)") (class "Default")
      (node (ref "J6") (pin "P2") (pinfunction "2_P2") (pintype "passive"))
    )
  )
)
